# homeboard7.net
KiCad netlist of a schematic drawn in EAGLE
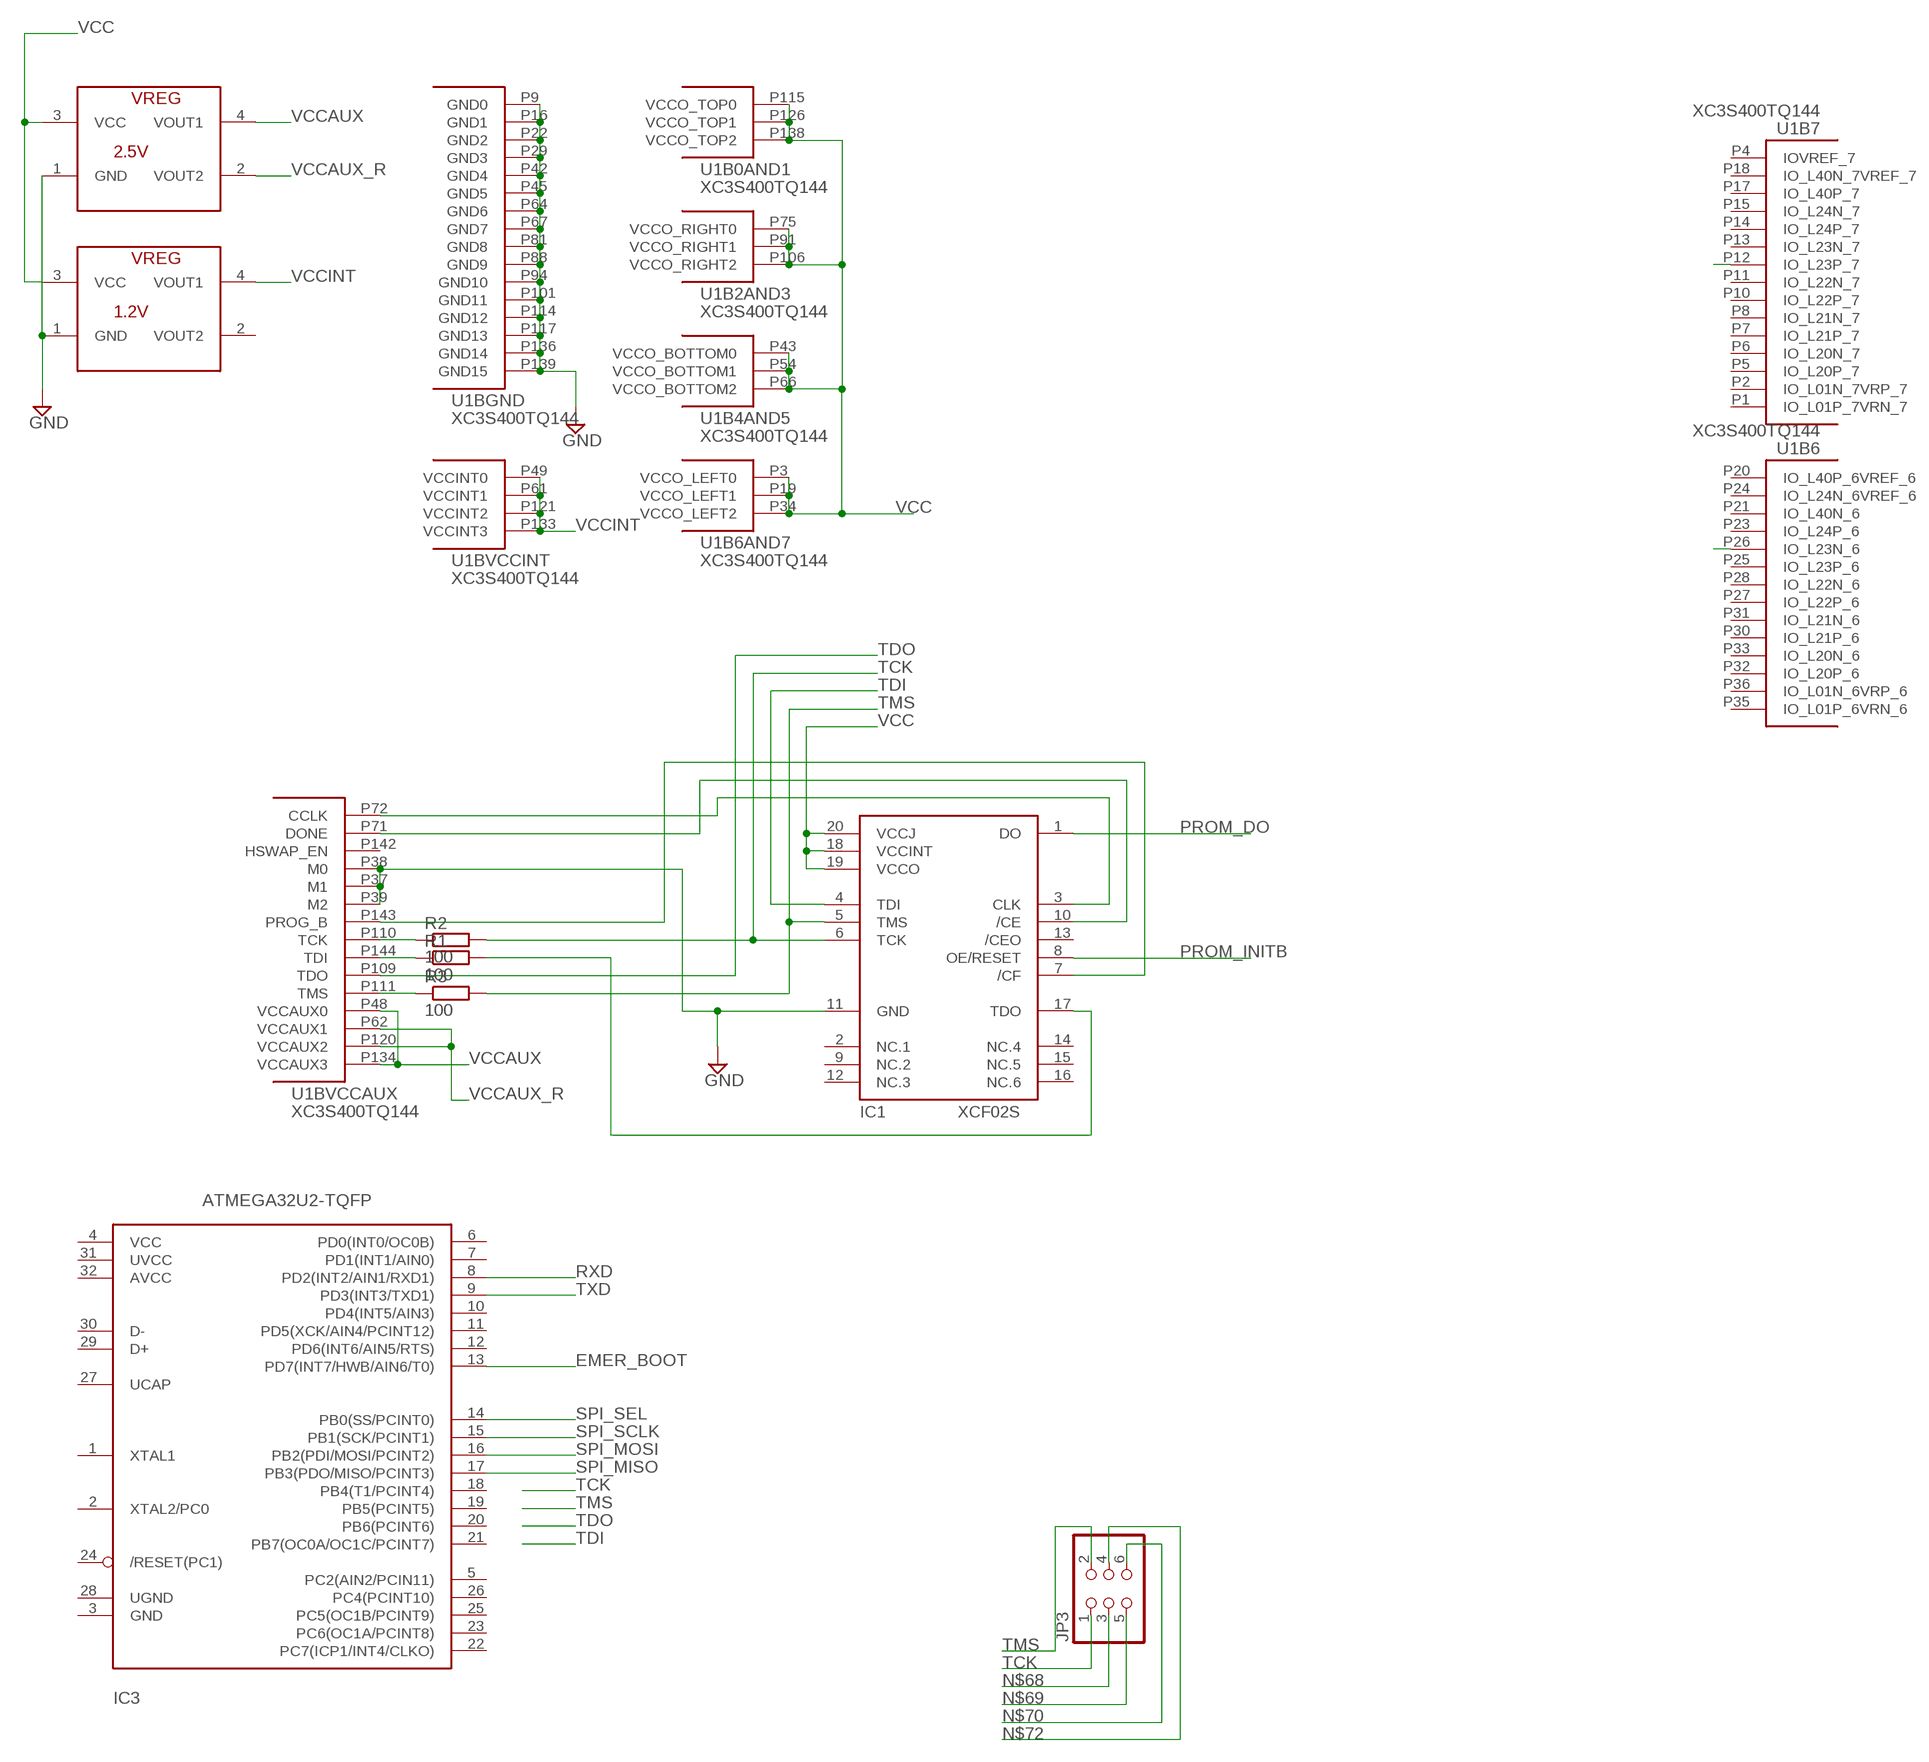
[diagram p0: schematic, sheet 1, part 1 of 3]
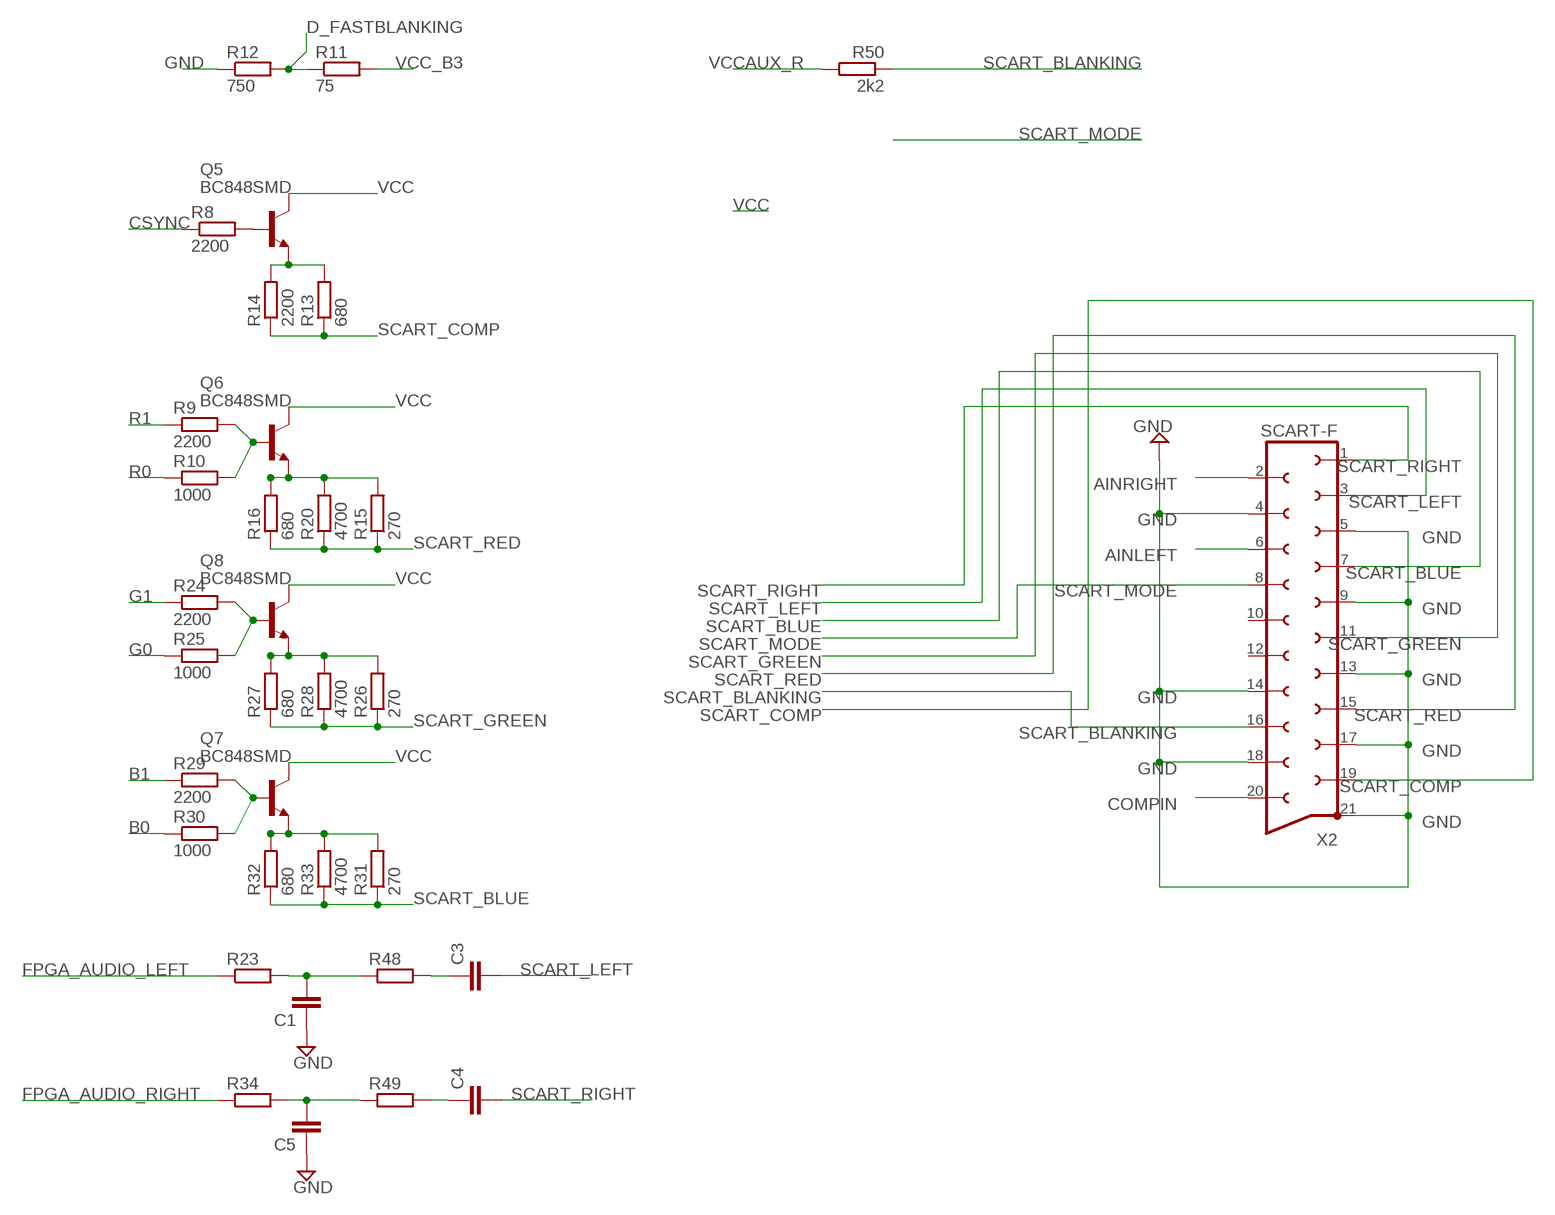
[diagram p1: schematic, sheet 1, part 2 of 3]
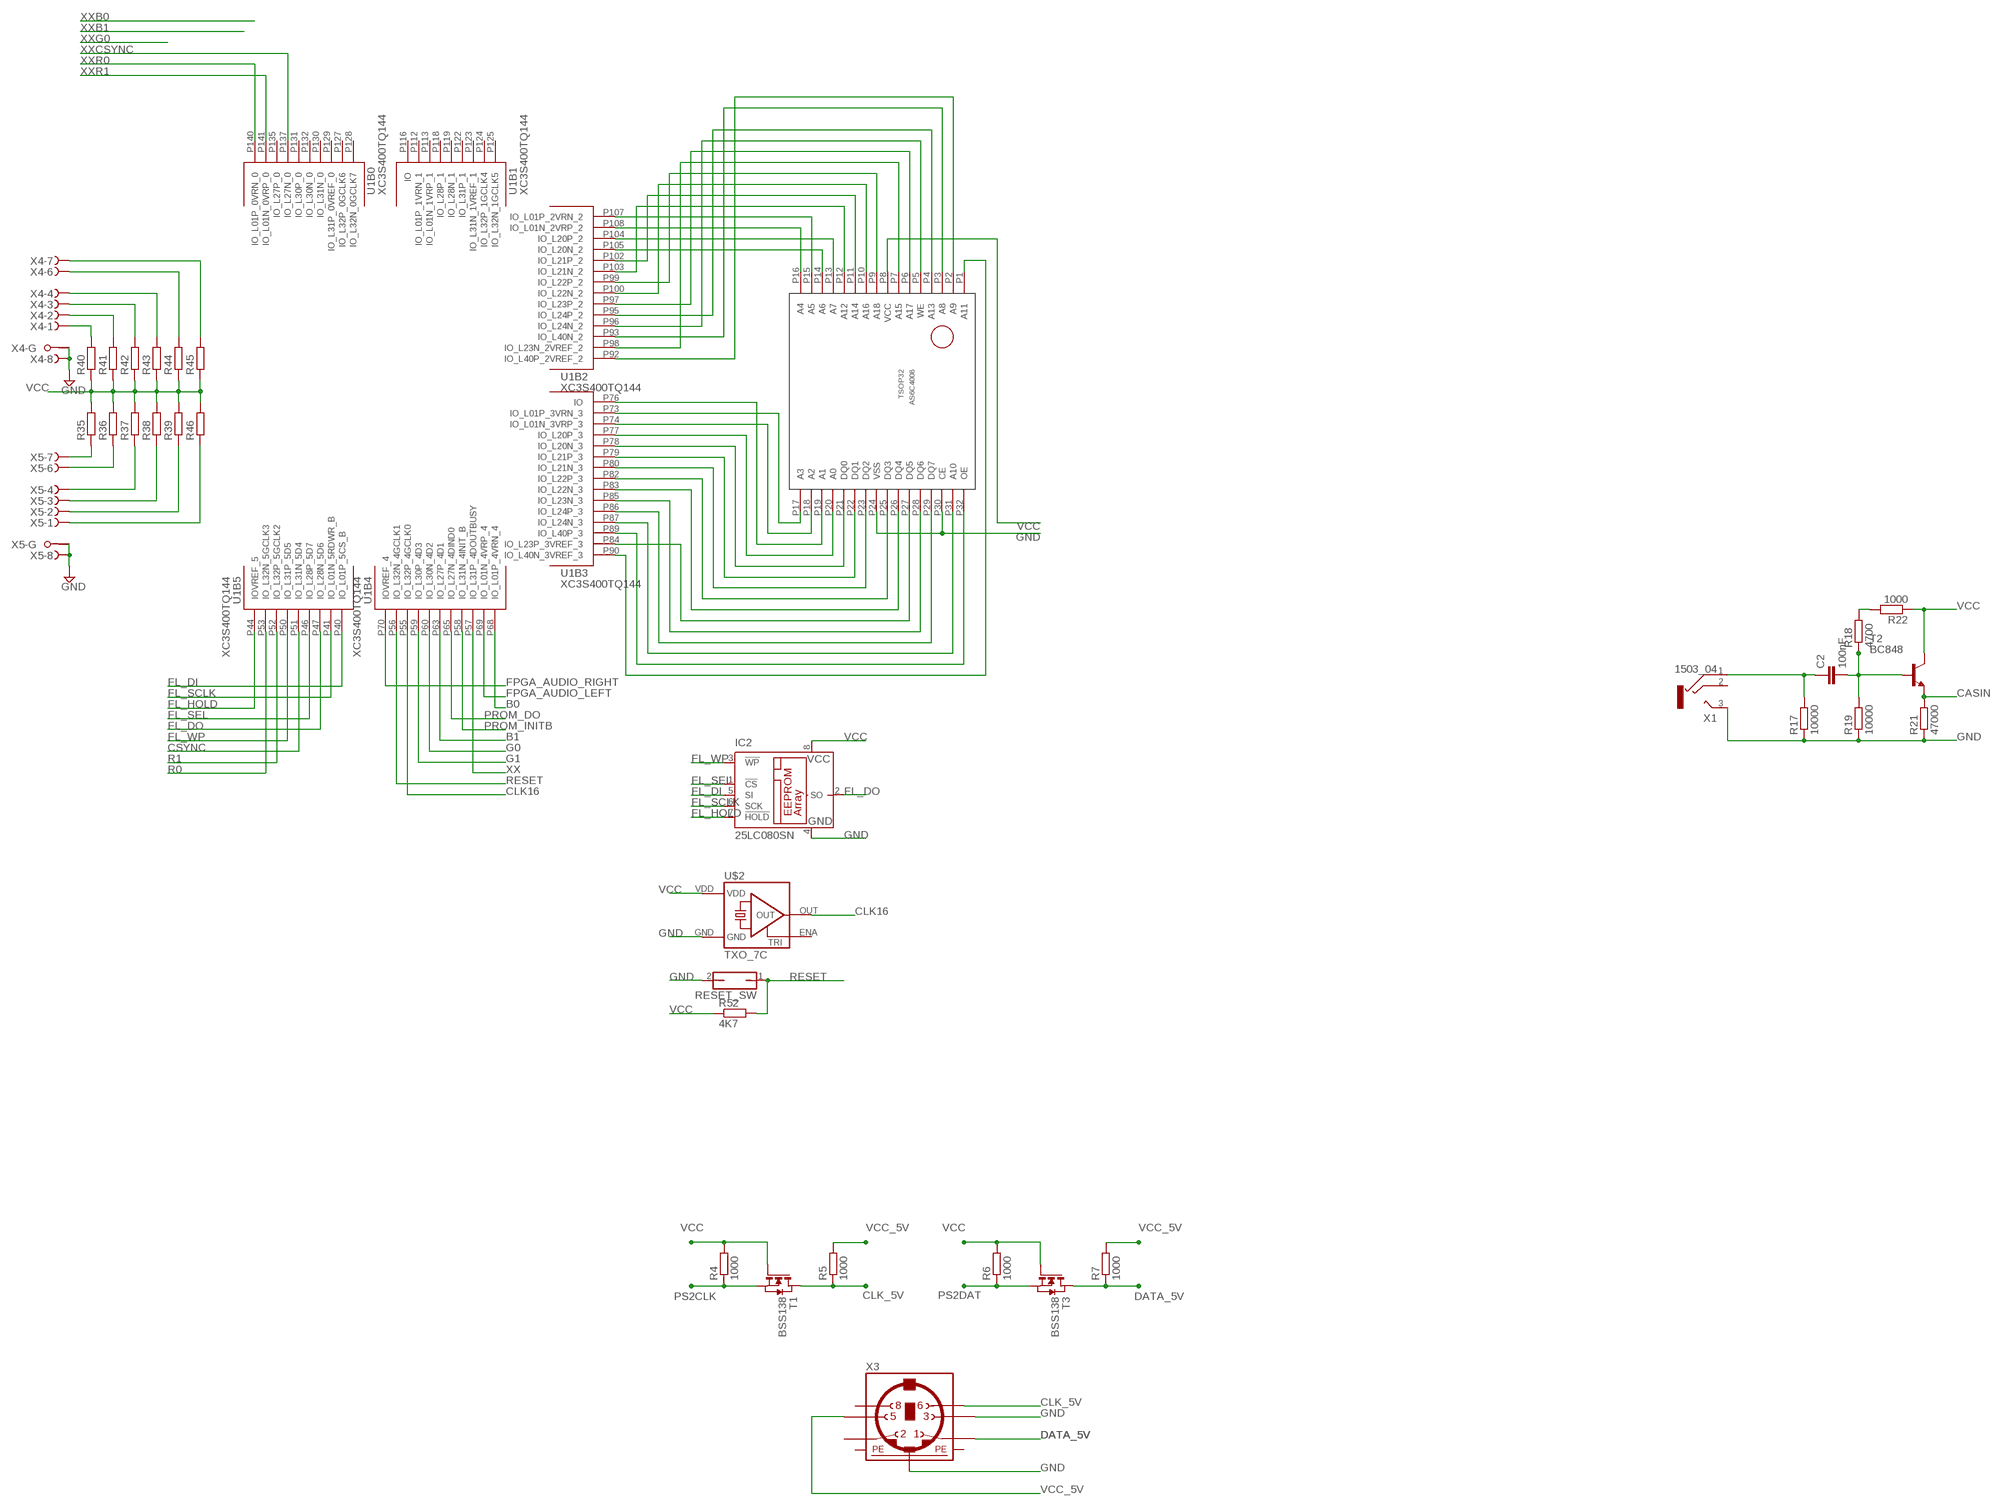
[diagram p2: schematic, sheet 1, part 3 of 3]

(export (version "E")
  (design (tool "Eeschema 10.0.6"))
  (components
    (comp (ref "C1")
      (value "C-EUC0603")
      (footprint "eagle-import:C0603")
      (libsource (lib "eagle-import") (part "C-EUC0603"))
    )
    (comp (ref "C2")
      (value "100nF")
      (footprint "eagle-import:C0603")
      (libsource (lib "eagle-import") (part "C-EUC0603"))
    )
    (comp (ref "C3")
      (value "C-EUC0603")
      (footprint "eagle-import:C0603")
      (libsource (lib "eagle-import") (part "C-EUC0603"))
    )
    (comp (ref "C4")
      (value "C-EUC0603")
      (footprint "eagle-import:C0603")
      (libsource (lib "eagle-import") (part "C-EUC0603"))
    )
    (comp (ref "C5")
      (value "C-EUC0603")
      (footprint "eagle-import:C0603")
      (libsource (lib "eagle-import") (part "C-EUC0603"))
    )
    (comp (ref "IC1")
      (value "XCF02S")
      (footprint "eagle-import:VO20")
      (libsource (lib "eagle-import") (part "XCF02S"))
    )
    (comp (ref "IC2")
      (value "25LC080SN")
      (footprint "eagle-import:SO-08")
      (fields (field (name "MF") "MICROCHIP") (field (name "MPN") "25LC080/SN"))
      (libsource (lib "eagle-import") (part "25SNLC080"))
    )
    (comp (ref "IC3")
      (value "ATMEGA32U2-TQFP")
      (footprint "eagle-import:TQFP32-08")
      (libsource (lib "eagle-import") (part "ATMEGA32U2-TQFP"))
    )
    (comp (ref "JP3")
      (value "PINHD-2X3")
      (footprint "eagle-import:2X03")
      (libsource (lib "eagle-import") (part "PINHD-2X3"))
    )
    (comp (ref "Q5")
      (value "BC848SMD")
      (footprint "eagle-import:SOT23")
      (libsource (lib "eagle-import") (part "BC848SMD"))
    )
    (comp (ref "Q6")
      (value "BC848SMD")
      (footprint "eagle-import:SOT23")
      (libsource (lib "eagle-import") (part "BC848SMD"))
    )
    (comp (ref "Q7")
      (value "BC848SMD")
      (footprint "eagle-import:SOT23")
      (libsource (lib "eagle-import") (part "BC848SMD"))
    )
    (comp (ref "Q8")
      (value "BC848SMD")
      (footprint "eagle-import:SOT23")
      (libsource (lib "eagle-import") (part "BC848SMD"))
    )
    (comp (ref "R1")
      (value "100")
      (footprint "eagle-import:R0805")
      (libsource (lib "eagle-import") (part "R-EU_R0805"))
    )
    (comp (ref "R2")
      (value "100")
      (footprint "eagle-import:R0805")
      (libsource (lib "eagle-import") (part "R-EU_R0805"))
    )
    (comp (ref "R3")
      (value "100")
      (footprint "eagle-import:R0805")
      (libsource (lib "eagle-import") (part "R-EU_R0805"))
    )
    (comp (ref "R4")
      (value "1000")
      (footprint "eagle-import:R0805")
      (libsource (lib "eagle-import") (part "R-EU_R0805"))
    )
    (comp (ref "R5")
      (value "1000")
      (footprint "eagle-import:R0805")
      (libsource (lib "eagle-import") (part "R-EU_R0805"))
    )
    (comp (ref "R6")
      (value "1000")
      (footprint "eagle-import:R0805")
      (libsource (lib "eagle-import") (part "R-EU_R0805"))
    )
    (comp (ref "R7")
      (value "1000")
      (footprint "eagle-import:R0805")
      (libsource (lib "eagle-import") (part "R-EU_R0805"))
    )
    (comp (ref "R8")
      (value "2200")
      (footprint "eagle-import:R0805")
      (libsource (lib "eagle-import") (part "R-EU_R0805"))
    )
    (comp (ref "R9")
      (value "2200")
      (footprint "eagle-import:R0805")
      (libsource (lib "eagle-import") (part "R-EU_R0805"))
    )
    (comp (ref "R10")
      (value "1000")
      (footprint "eagle-import:R0805")
      (libsource (lib "eagle-import") (part "R-EU_R0805"))
    )
    (comp (ref "R11")
      (value "75")
      (footprint "eagle-import:R0805")
      (libsource (lib "eagle-import") (part "R-EU_R0805"))
    )
    (comp (ref "R12")
      (value "750")
      (footprint "eagle-import:R0805")
      (libsource (lib "eagle-import") (part "R-EU_R0805"))
    )
    (comp (ref "R13")
      (value "680")
      (footprint "eagle-import:R0805")
      (libsource (lib "eagle-import") (part "R-EU_R0805"))
    )
    (comp (ref "R14")
      (value "2200")
      (footprint "eagle-import:R0805")
      (libsource (lib "eagle-import") (part "R-EU_R0805"))
    )
    (comp (ref "R15")
      (value "270")
      (footprint "eagle-import:R0805")
      (libsource (lib "eagle-import") (part "R-EU_R0805"))
    )
    (comp (ref "R16")
      (value "680")
      (footprint "eagle-import:R0805")
      (libsource (lib "eagle-import") (part "R-EU_R0805"))
    )
    (comp (ref "R17")
      (value "10000")
      (footprint "eagle-import:R0805")
      (libsource (lib "eagle-import") (part "R-EU_R0805"))
    )
    (comp (ref "R18")
      (value "4700")
      (footprint "eagle-import:R0805")
      (libsource (lib "eagle-import") (part "R-EU_R0805"))
    )
    (comp (ref "R19")
      (value "10000")
      (footprint "eagle-import:R0805")
      (libsource (lib "eagle-import") (part "R-EU_R0805"))
    )
    (comp (ref "R20")
      (value "4700")
      (footprint "eagle-import:R0805")
      (libsource (lib "eagle-import") (part "R-EU_R0805"))
    )
    (comp (ref "R21")
      (value "47000")
      (footprint "eagle-import:R0805")
      (libsource (lib "eagle-import") (part "R-EU_R0805"))
    )
    (comp (ref "R22")
      (value "1000")
      (footprint "eagle-import:R0805")
      (libsource (lib "eagle-import") (part "R-EU_R0805"))
    )
    (comp (ref "R23")
      (value "R-EU_M0805")
      (footprint "eagle-import:M0805")
      (libsource (lib "eagle-import") (part "resistor_R-EU_M0805"))
    )
    (comp (ref "R24")
      (value "2200")
      (footprint "eagle-import:R0805")
      (libsource (lib "eagle-import") (part "R-EU_R0805"))
    )
    (comp (ref "R25")
      (value "1000")
      (footprint "eagle-import:R0805")
      (libsource (lib "eagle-import") (part "R-EU_R0805"))
    )
    (comp (ref "R26")
      (value "270")
      (footprint "eagle-import:R0805")
      (libsource (lib "eagle-import") (part "R-EU_R0805"))
    )
    (comp (ref "R27")
      (value "680")
      (footprint "eagle-import:R0805")
      (libsource (lib "eagle-import") (part "R-EU_R0805"))
    )
    (comp (ref "R28")
      (value "4700")
      (footprint "eagle-import:R0805")
      (libsource (lib "eagle-import") (part "R-EU_R0805"))
    )
    (comp (ref "R29")
      (value "2200")
      (footprint "eagle-import:R0805")
      (libsource (lib "eagle-import") (part "R-EU_R0805"))
    )
    (comp (ref "R30")
      (value "1000")
      (footprint "eagle-import:R0805")
      (libsource (lib "eagle-import") (part "R-EU_R0805"))
    )
    (comp (ref "R31")
      (value "270")
      (footprint "eagle-import:R0805")
      (libsource (lib "eagle-import") (part "R-EU_R0805"))
    )
    (comp (ref "R32")
      (value "680")
      (footprint "eagle-import:R0805")
      (libsource (lib "eagle-import") (part "R-EU_R0805"))
    )
    (comp (ref "R33")
      (value "4700")
      (footprint "eagle-import:R0805")
      (libsource (lib "eagle-import") (part "R-EU_R0805"))
    )
    (comp (ref "R34")
      (value "R-EU_M0805")
      (footprint "eagle-import:M0805")
      (libsource (lib "eagle-import") (part "resistor_R-EU_M0805"))
    )
    (comp (ref "R35")
      (value "R-EU_M0805")
      (footprint "eagle-import:M0805")
      (libsource (lib "eagle-import") (part "resistor_R-EU_M0805"))
    )
    (comp (ref "R36")
      (value "R-EU_M0805")
      (footprint "eagle-import:M0805")
      (libsource (lib "eagle-import") (part "resistor_R-EU_M0805"))
    )
    (comp (ref "R37")
      (value "R-EU_M0805")
      (footprint "eagle-import:M0805")
      (libsource (lib "eagle-import") (part "resistor_R-EU_M0805"))
    )
    (comp (ref "R38")
      (value "R-EU_M0805")
      (footprint "eagle-import:M0805")
      (libsource (lib "eagle-import") (part "resistor_R-EU_M0805"))
    )
    (comp (ref "R39")
      (value "R-EU_M0805")
      (footprint "eagle-import:M0805")
      (libsource (lib "eagle-import") (part "resistor_R-EU_M0805"))
    )
    (comp (ref "R40")
      (value "R-EU_M0805")
      (footprint "eagle-import:M0805")
      (libsource (lib "eagle-import") (part "resistor_R-EU_M0805"))
    )
    (comp (ref "R41")
      (value "R-EU_M0805")
      (footprint "eagle-import:M0805")
      (libsource (lib "eagle-import") (part "resistor_R-EU_M0805"))
    )
    (comp (ref "R42")
      (value "R-EU_M0805")
      (footprint "eagle-import:M0805")
      (libsource (lib "eagle-import") (part "resistor_R-EU_M0805"))
    )
    (comp (ref "R43")
      (value "R-EU_M0805")
      (footprint "eagle-import:M0805")
      (libsource (lib "eagle-import") (part "resistor_R-EU_M0805"))
    )
    (comp (ref "R44")
      (value "R-EU_M0805")
      (footprint "eagle-import:M0805")
      (libsource (lib "eagle-import") (part "resistor_R-EU_M0805"))
    )
    (comp (ref "R45")
      (value "R-EU_M0805")
      (footprint "eagle-import:M0805")
      (libsource (lib "eagle-import") (part "resistor_R-EU_M0805"))
    )
    (comp (ref "R46")
      (value "R-EU_M0805")
      (footprint "eagle-import:M0805")
      (libsource (lib "eagle-import") (part "resistor_R-EU_M0805"))
    )
    (comp (ref "R48")
      (value "R-EU_M0805")
      (footprint "eagle-import:M0805")
      (libsource (lib "eagle-import") (part "resistor_R-EU_M0805"))
    )
    (comp (ref "R49")
      (value "R-EU_M0805")
      (footprint "eagle-import:M0805")
      (libsource (lib "eagle-import") (part "resistor_R-EU_M0805"))
    )
    (comp (ref "R50")
      (value "2k2")
      (footprint "eagle-import:M0805")
      (libsource (lib "eagle-import") (part "resistor_R-EU_M0805"))
    )
    (comp (ref "R52")
      (value "4K7")
      (footprint "eagle-import:M0805")
      (libsource (lib "eagle-import") (part "resistor_R-EU_M0805"))
    )
    (comp (ref "REG1.2")
      (value "1.2V")
      (footprint "eagle-import:SOT223")
      (libsource (lib "eagle-import") (part "NX1117"))
    )
    (comp (ref "REG2.5")
      (value "2.5V")
      (footprint "eagle-import:SOT223")
      (libsource (lib "eagle-import") (part "NX1117"))
    )
    (comp (ref "RESET_SW")
      (value "JP1Q")
      (footprint "eagle-import:JP1")
      (libsource (lib "eagle-import") (part "JP1Q"))
    )
    (comp (ref "T1")
      (value "BSS138")
      (footprint "eagle-import:SOT-23")
      (libsource (lib "eagle-import") (part "NMOSSOT23"))
    )
    (comp (ref "T2")
      (value "BC848")
      (footprint "eagle-import:SOT23")
      (libsource (lib "eagle-import") (part "BC848"))
    )
    (comp (ref "T3")
      (value "BSS138")
      (footprint "eagle-import:SOT-23")
      (libsource (lib "eagle-import") (part "NMOSSOT23"))
    )
    (comp (ref "U$1")
      (value "AS6C4008")
      (footprint "eagle-import:TSOP32")
      (libsource (lib "eagle-import") (part "AS6C4008"))
    )
    (comp (ref "U$2")
      (value "TXO_7C")
      (footprint "eagle-import:OSC_7C")
      (libsource (lib "eagle-import") (part "TXO_7C"))
    )
    (comp (ref "U1")
      (value "XC3S400TQ144")
      (footprint "eagle-import:TQ144")
      (libsource (lib "eagle-import") (part "XC3S400TQ144"))
    )
    (comp (ref "X1")
      (value "1503_04")
      (footprint "eagle-import:1503_04")
      (libsource (lib "eagle-import") (part "1503_04"))
    )
    (comp (ref "X2")
      (value "SCART-F")
      (footprint "eagle-import:SCART-F")
      (libsource (lib "eagle-import") (part "SCART-F"))
    )
    (comp (ref "X3")
      (value "MINI_DIN_6")
      (footprint "eagle-import:M_DIN6")
      (libsource (lib "eagle-import") (part "MINI_DIN_6"))
    )
    (comp (ref "X4")
      (value "F09HPS")
      (footprint "eagle-import:F09HP")
      (libsource (lib "eagle-import") (part "F09HPS"))
    )
    (comp (ref "X5")
      (value "F09HPS")
      (footprint "eagle-import:F09HP")
      (libsource (lib "eagle-import") (part "F09HPS"))
    )
  )
  (nets
    (net (code "1") (name "/AINLEFT") (class "Default")
      (node (ref "X2") (pin "6") (pinfunction "6_6") (pintype "passive"))
    )
    (net (code "2") (name "/AINRIGHT") (class "Default")
      (node (ref "X2") (pin "2") (pinfunction "2_2") (pintype "passive"))
    )
    (net (code "3") (name "/B0") (class "Default")
      (node (ref "R30") (pin "1") (pinfunction "1_1") (pintype "passive"))
      (node (ref "U1") (pin "P68") (pinfunction "IO_L01P_4VRN_4_P68") (pintype "bidirectional"))
    )
    (net (code "4") (name "/B1") (class "Default")
      (node (ref "R29") (pin "1") (pinfunction "1_1") (pintype "passive"))
      (node (ref "U1") (pin "P63") (pinfunction "IO_L27P_4D1_P63") (pintype "bidirectional"))
    )
    (net (code "5") (name "/CASIN") (class "Default")
      (node (ref "R21") (pin "2") (pinfunction "2_2") (pintype "passive"))
      (node (ref "T2") (pin "2") (pinfunction "E_2") (pintype "passive"))
    )
    (net (code "6") (name "/CLK16") (class "Default")
      (node (ref "U$2") (pin "OUT") (pinfunction "OUT_OUT") (pintype "output"))
      (node (ref "U1") (pin "P55") (pinfunction "IO_L32P_4GCLK0_P55") (pintype "bidirectional"))
    )
    (net (code "7") (name "/CLK_5V") (class "Default")
      (node (ref "R5") (pin "1") (pinfunction "1_1") (pintype "passive"))
      (node (ref "T1") (pin "1") (pinfunction "D_1") (pintype "passive"))
      (node (ref "X3") (pin "6") (pinfunction "6_6") (pintype "passive"))
    )
    (net (code "8") (name "/COMPIN") (class "Default")
      (node (ref "X2") (pin "20") (pinfunction "20_20") (pintype "passive"))
    )
    (net (code "9") (name "/CSYNC") (class "Default")
      (node (ref "R8") (pin "1") (pinfunction "1_1") (pintype "passive"))
      (node (ref "U1") (pin "P51") (pinfunction "IO_L31N_5D4_P51") (pintype "bidirectional"))
    )
    (net (code "10") (name "/DATA_5V") (class "Default")
      (node (ref "R7") (pin "1") (pinfunction "1_1") (pintype "passive"))
      (node (ref "T3") (pin "1") (pinfunction "D_1") (pintype "passive"))
      (node (ref "X3") (pin "1") (pinfunction "1_1") (pintype "passive"))
    )
    (net (code "11") (name "/D_FASTBLANKING") (class "Default")
      (node (ref "R11") (pin "1") (pinfunction "1_1") (pintype "passive"))
      (node (ref "R12") (pin "2") (pinfunction "2_2") (pintype "passive"))
    )
    (net (code "12") (name "/EMER_BOOT") (class "Default")
      (node (ref "IC3") (pin "13") (pinfunction "PD7(INT7/HWB/AIN6/T0)_13") (pintype "bidirectional"))
    )
    (net (code "13") (name "/FL_DI") (class "Default")
      (node (ref "IC2") (pin "5") (pinfunction "SI_5") (pintype "input"))
      (node (ref "U1") (pin "P40") (pinfunction "IO_L01P_5CS_B_P40") (pintype "bidirectional"))
    )
    (net (code "14") (name "/FL_DO") (class "Default")
      (node (ref "IC2") (pin "2") (pinfunction "SO_2") (pintype "bidirectional"))
      (node (ref "U1") (pin "P47") (pinfunction "IO_L28N_5D6_P47") (pintype "bidirectional"))
    )
    (net (code "15") (name "/FL_HOLD") (class "Default")
      (node (ref "IC2") (pin "7") (pinfunction "~{HOLD}_7") (pintype "input"))
      (node (ref "U1") (pin "P44") (pinfunction "IOVREF_5_P44") (pintype "bidirectional"))
    )
    (net (code "16") (name "/FL_SCLK") (class "Default")
      (node (ref "IC2") (pin "6") (pinfunction "SCK_6") (pintype "input"))
      (node (ref "U1") (pin "P41") (pinfunction "IO_L01N_5RDWR_B_P41") (pintype "bidirectional"))
    )
    (net (code "17") (name "/FL_SEL") (class "Default")
      (node (ref "IC2") (pin "1") (pinfunction "~{CS}_1") (pintype "input"))
      (node (ref "U1") (pin "P46") (pinfunction "IO_L28P_5D7_P46") (pintype "bidirectional"))
    )
    (net (code "18") (name "/FL_WP") (class "Default")
      (node (ref "IC2") (pin "3") (pinfunction "~{WP}_3") (pintype "input"))
      (node (ref "U1") (pin "P50") (pinfunction "IO_L31P_5D5_P50") (pintype "bidirectional"))
    )
    (net (code "19") (name "/FPGA_AUDIO_LEFT") (class "Default")
      (node (ref "R23") (pin "1") (pinfunction "1_1") (pintype "passive"))
      (node (ref "U1") (pin "P69") (pinfunction "IO_L01N_4VRP_4_P69") (pintype "bidirectional"))
    )
    (net (code "20") (name "/FPGA_AUDIO_RIGHT") (class "Default")
      (node (ref "R34") (pin "1") (pinfunction "1_1") (pintype "passive"))
      (node (ref "U1") (pin "P70") (pinfunction "IOVREF_4_P70") (pintype "bidirectional"))
    )
    (net (code "21") (name "/G0") (class "Default")
      (node (ref "R25") (pin "1") (pinfunction "1_1") (pintype "passive"))
      (node (ref "U1") (pin "P60") (pinfunction "IO_L30N_4D2_P60") (pintype "bidirectional"))
    )
    (net (code "22") (name "/G1") (class "Default")
      (node (ref "R24") (pin "1") (pinfunction "1_1") (pintype "passive"))
      (node (ref "U1") (pin "P59") (pinfunction "IO_L30P_4D3_P59") (pintype "bidirectional"))
    )
    (net (code "23") (name "/N$68") (class "Default")
      (node (ref "JP3") (pin "3") (pinfunction "3_3") (pintype "passive"))
    )
    (net (code "24") (name "/N$69") (class "Default")
      (node (ref "JP3") (pin "5") (pinfunction "5_5") (pintype "passive"))
    )
    (net (code "25") (name "/N$70") (class "Default")
      (node (ref "JP3") (pin "6") (pinfunction "6_6") (pintype "passive"))
    )
    (net (code "26") (name "/N$72") (class "Default")
      (node (ref "JP3") (pin "4") (pinfunction "4_4") (pintype "passive"))
    )
    (net (code "27") (name "/PE1") (class "Default")
      (node (ref "X3") (pin "SH1") (pinfunction "PE1_SH1") (pintype "power_in"))
    )
    (net (code "28") (name "/PE3") (class "Default")
      (node (ref "X3") (pin "SH3") (pinfunction "PE3_SH3") (pintype "power_in"))
    )
    (net (code "29") (name "/PROM_DO") (class "Default")
      (node (ref "IC1") (pin "1") (pinfunction "DO_1") (pintype "bidirectional"))
      (node (ref "U1") (pin "P65") (pinfunction "IO_L27N_4DIND0_P65") (pintype "bidirectional"))
    )
    (net (code "30") (name "/PROM_INITB") (class "Default")
      (node (ref "IC1") (pin "8") (pinfunction "OE/RESET_8") (pintype "bidirectional"))
      (node (ref "U1") (pin "P58") (pinfunction "IO_L31N_4INIT_B_P58") (pintype "bidirectional"))
    )
    (net (code "31") (name "/PS2CLK") (class "Default")
      (node (ref "R4") (pin "1") (pinfunction "1_1") (pintype "passive"))
      (node (ref "T1") (pin "2") (pinfunction "S_2") (pintype "passive"))
    )
    (net (code "32") (name "/PS2DAT") (class "Default")
      (node (ref "R6") (pin "1") (pinfunction "1_1") (pintype "passive"))
      (node (ref "T3") (pin "2") (pinfunction "S_2") (pintype "passive"))
    )
    (net (code "33") (name "/R0") (class "Default")
      (node (ref "R10") (pin "1") (pinfunction "1_1") (pintype "passive"))
      (node (ref "U1") (pin "P53") (pinfunction "IO_L32N_5GCLK3_P53") (pintype "bidirectional"))
    )
    (net (code "34") (name "/R1") (class "Default")
      (node (ref "R9") (pin "1") (pinfunction "1_1") (pintype "passive"))
      (node (ref "U1") (pin "P52") (pinfunction "IO_L32P_5GCLK2_P52") (pintype "bidirectional"))
    )
    (net (code "35") (name "/RESET") (class "Default")
      (node (ref "R52") (pin "2") (pinfunction "2_2") (pintype "passive"))
      (node (ref "RESET_SW") (pin "1") (pinfunction "1_1") (pintype "passive"))
      (node (ref "U1") (pin "P56") (pinfunction "IO_L32N_4GCLK1_P56") (pintype "bidirectional"))
    )
    (net (code "36") (name "/RXD") (class "Default")
      (node (ref "IC3") (pin "8") (pinfunction "PD2(INT2/AIN1/RXD1)_8") (pintype "bidirectional"))
    )
    (net (code "37") (name "/SCART_BLANKING") (class "Default")
      (node (ref "R50") (pin "1") (pinfunction "1_1") (pintype "passive"))
      (node (ref "X2") (pin "16") (pinfunction "16_16") (pintype "passive"))
    )
    (net (code "38") (name "/SCART_BLUE") (class "Default")
      (node (ref "R31") (pin "1") (pinfunction "1_1") (pintype "passive"))
      (node (ref "R32") (pin "1") (pinfunction "1_1") (pintype "passive"))
      (node (ref "R33") (pin "1") (pinfunction "1_1") (pintype "passive"))
      (node (ref "X2") (pin "7") (pinfunction "7_7") (pintype "passive"))
    )
    (net (code "39") (name "/SCART_COMP") (class "Default")
      (node (ref "R13") (pin "1") (pinfunction "1_1") (pintype "passive"))
      (node (ref "R14") (pin "1") (pinfunction "1_1") (pintype "passive"))
      (node (ref "X2") (pin "19") (pinfunction "19_19") (pintype "passive"))
    )
    (net (code "40") (name "/SCART_GREEN") (class "Default")
      (node (ref "R26") (pin "1") (pinfunction "1_1") (pintype "passive"))
      (node (ref "R27") (pin "1") (pinfunction "1_1") (pintype "passive"))
      (node (ref "R28") (pin "1") (pinfunction "1_1") (pintype "passive"))
      (node (ref "X2") (pin "11") (pinfunction "11_11") (pintype "passive"))
    )
    (net (code "41") (name "/SCART_LEFT") (class "Default")
      (node (ref "C3") (pin "2") (pinfunction "2_2") (pintype "passive"))
      (node (ref "X2") (pin "3") (pinfunction "3_3") (pintype "passive"))
    )
    (net (code "42") (name "/SCART_MODE") (class "Default")
      (node (ref "X2") (pin "8") (pinfunction "8_8") (pintype "passive"))
    )
    (net (code "43") (name "/SCART_RED") (class "Default")
      (node (ref "R15") (pin "1") (pinfunction "1_1") (pintype "passive"))
      (node (ref "R16") (pin "1") (pinfunction "1_1") (pintype "passive"))
      (node (ref "R20") (pin "1") (pinfunction "1_1") (pintype "passive"))
      (node (ref "X2") (pin "15") (pinfunction "15_15") (pintype "passive"))
    )
    (net (code "44") (name "/SCART_RIGHT") (class "Default")
      (node (ref "C4") (pin "2") (pinfunction "2_2") (pintype "passive"))
      (node (ref "X2") (pin "1") (pinfunction "1_1") (pintype "passive"))
    )
    (net (code "45") (name "/SPI_MISO") (class "Default")
      (node (ref "IC3") (pin "17") (pinfunction "PB3(PDO/MISO/PCINT3)_17") (pintype "bidirectional"))
    )
    (net (code "46") (name "/SPI_MOSI") (class "Default")
      (node (ref "IC3") (pin "16") (pinfunction "PB2(PDI/MOSI/PCINT2)_16") (pintype "bidirectional"))
    )
    (net (code "47") (name "/SPI_SCLK") (class "Default")
      (node (ref "IC3") (pin "15") (pinfunction "PB1(SCK/PCINT1)_15") (pintype "bidirectional"))
    )
    (net (code "48") (name "/SPI_SEL") (class "Default")
      (node (ref "IC3") (pin "14") (pinfunction "PB0(SS/PCINT0)_14") (pintype "bidirectional"))
    )
    (net (code "49") (name "/TCK") (class "Default")
      (node (ref "IC1") (pin "6") (pinfunction "TCK_6") (pintype "bidirectional"))
      (node (ref "JP3") (pin "1") (pinfunction "1_1") (pintype "passive"))
      (node (ref "R2") (pin "2") (pinfunction "2_2") (pintype "passive"))
    )
    (net (code "50") (name "/TDI") (class "Default")
      (node (ref "IC1") (pin "4") (pinfunction "TDI_4") (pintype "bidirectional"))
    )
    (net (code "51") (name "/TDO") (class "Default")
      (node (ref "U1") (pin "P109") (pinfunction "TDO_P109") (pintype "bidirectional"))
    )
    (net (code "52") (name "/TMS") (class "Default")
      (node (ref "IC1") (pin "5") (pinfunction "TMS_5") (pintype "bidirectional"))
      (node (ref "JP3") (pin "2") (pinfunction "2_2") (pintype "passive"))
      (node (ref "R3") (pin "2") (pinfunction "2_2") (pintype "passive"))
    )
    (net (code "53") (name "/TXD") (class "Default")
      (node (ref "IC3") (pin "9") (pinfunction "PD3(INT3/TXD1)_9") (pintype "bidirectional"))
    )
    (net (code "54") (name "/VCC") (class "Default")
      (node (ref "IC1") (pin "18") (pinfunction "VCCINT_18") (pintype "bidirectional"))
      (node (ref "IC1") (pin "19") (pinfunction "VCCO_19") (pintype "bidirectional"))
      (node (ref "IC1") (pin "20") (pinfunction "VCCJ_20") (pintype "bidirectional"))
      (node (ref "IC2") (pin "8") (pinfunction "VCC_8") (pintype "power_in"))
      (node (ref "Q5") (pin "3") (pinfunction "C_3") (pintype "passive"))
      (node (ref "Q6") (pin "3") (pinfunction "C_3") (pintype "passive"))
      (node (ref "Q7") (pin "3") (pinfunction "C_3") (pintype "passive"))
      (node (ref "Q8") (pin "3") (pinfunction "C_3") (pintype "passive"))
      (node (ref "R22") (pin "1") (pinfunction "1_1") (pintype "passive"))
      (node (ref "R35") (pin "2") (pinfunction "2_2") (pintype "passive"))
      (node (ref "R36") (pin "2") (pinfunction "2_2") (pintype "passive"))
      (node (ref "R37") (pin "2") (pinfunction "2_2") (pintype "passive"))
      (node (ref "R38") (pin "2") (pinfunction "2_2") (pintype "passive"))
      (node (ref "R39") (pin "2") (pinfunction "2_2") (pintype "passive"))
      (node (ref "R4") (pin "2") (pinfunction "2_2") (pintype "passive"))
      (node (ref "R40") (pin "1") (pinfunction "1_1") (pintype "passive"))
      (node (ref "R41") (pin "1") (pinfunction "1_1") (pintype "passive"))
      (node (ref "R42") (pin "1") (pinfunction "1_1") (pintype "passive"))
      (node (ref "R43") (pin "1") (pinfunction "1_1") (pintype "passive"))
      (node (ref "R44") (pin "1") (pinfunction "1_1") (pintype "passive"))
      (node (ref "R45") (pin "1") (pinfunction "1_1") (pintype "passive"))
      (node (ref "R46") (pin "2") (pinfunction "2_2") (pintype "passive"))
      (node (ref "R52") (pin "1") (pinfunction "1_1") (pintype "passive"))
      (node (ref "R6") (pin "2") (pinfunction "2_2") (pintype "passive"))
      (node (ref "REG1.2") (pin "3") (pinfunction "VCC_3") (pintype "bidirectional"))
      (node (ref "REG2.5") (pin "3") (pinfunction "VCC_3") (pintype "bidirectional"))
      (node (ref "T1") (pin "3") (pinfunction "G_3") (pintype "passive"))
      (node (ref "T2") (pin "3") (pinfunction "C_3") (pintype "passive"))
      (node (ref "T3") (pin "3") (pinfunction "G_3") (pintype "passive"))
      (node (ref "U$1") (pin "P8") (pinfunction "VCC_P8") (pintype "bidirectional"))
      (node (ref "U$2") (pin "VDD") (pinfunction "VDD_VDD") (pintype "power_in"))
      (node (ref "U1") (pin "P106") (pinfunction "VCCO_RIGHT2_P106") (pintype "passive"))
      (node (ref "U1") (pin "P115") (pinfunction "VCCO_TOP0_P115") (pintype "passive"))
      (node (ref "U1") (pin "P126") (pinfunction "VCCO_TOP1_P126") (pintype "passive"))
      (node (ref "U1") (pin "P138") (pinfunction "VCCO_TOP2_P138") (pintype "passive"))
      (node (ref "U1") (pin "P19") (pinfunction "VCCO_LEFT1_P19") (pintype "passive"))
      (node (ref "U1") (pin "P3") (pinfunction "VCCO_LEFT0_P3") (pintype "passive"))
      (node (ref "U1") (pin "P34") (pinfunction "VCCO_LEFT2_P34") (pintype "passive"))
      (node (ref "U1") (pin "P43") (pinfunction "VCCO_BOTTOM0_P43") (pintype "passive"))
      (node (ref "U1") (pin "P54") (pinfunction "VCCO_BOTTOM1_P54") (pintype "passive"))
      (node (ref "U1") (pin "P66") (pinfunction "VCCO_BOTTOM2_P66") (pintype "passive"))
      (node (ref "U1") (pin "P75") (pinfunction "VCCO_RIGHT0_P75") (pintype "passive"))
      (node (ref "U1") (pin "P91") (pinfunction "VCCO_RIGHT1_P91") (pintype "passive"))
    )
    (net (code "55") (name "/VCCAUX") (class "Default")
      (node (ref "REG2.5") (pin "4") (pinfunction "VOUT1_4") (pintype "bidirectional"))
      (node (ref "U1") (pin "P134") (pinfunction "VCCAUX3_P134") (pintype "passive"))
      (node (ref "U1") (pin "P48") (pinfunction "VCCAUX0_P48") (pintype "passive"))
    )
    (net (code "56") (name "/VCCAUX_R") (class "Default")
      (node (ref "R50") (pin "2") (pinfunction "2_2") (pintype "passive"))
      (node (ref "REG2.5") (pin "2") (pinfunction "VOUT2_2") (pintype "bidirectional"))
      (node (ref "U1") (pin "P120") (pinfunction "VCCAUX2_P120") (pintype "passive"))
      (node (ref "U1") (pin "P62") (pinfunction "VCCAUX1_P62") (pintype "passive"))
    )
    (net (code "57") (name "/VCCINT") (class "Default")
      (node (ref "REG1.2") (pin "4") (pinfunction "VOUT1_4") (pintype "bidirectional"))
      (node (ref "U1") (pin "P121") (pinfunction "VCCINT2_P121") (pintype "passive"))
      (node (ref "U1") (pin "P133") (pinfunction "VCCINT3_P133") (pintype "passive"))
      (node (ref "U1") (pin "P49") (pinfunction "VCCINT0_P49") (pintype "passive"))
      (node (ref "U1") (pin "P61") (pinfunction "VCCINT1_P61") (pintype "passive"))
    )
    (net (code "58") (name "/VCC_5V") (class "Default")
      (node (ref "R5") (pin "2") (pinfunction "2_2") (pintype "passive"))
      (node (ref "R7") (pin "2") (pinfunction "2_2") (pintype "passive"))
      (node (ref "X3") (pin "5") (pinfunction "5_5") (pintype "passive"))
    )
    (net (code "59") (name "/VCC_B3") (class "Default")
      (node (ref "R11") (pin "2") (pinfunction "2_2") (pintype "passive"))
    )
    (net (code "60") (name "/XX") (class "Default")
      (node (ref "U1") (pin "P57") (pinfunction "IO_L31P_4DOUTBUSY_P57") (pintype "bidirectional"))
    )
    (net (code "63") (name "/XXCSYNC") (class "Default")
      (node (ref "U1") (pin "P137") (pinfunction "IO_L27N_0_P137") (pintype "bidirectional"))
    )
    (net (code "65") (name "/XXR0") (class "Default")
      (node (ref "U1") (pin "P140") (pinfunction "IO_L01P_0VRN_0_P140") (pintype "bidirectional"))
    )
    (net (code "66") (name "/XXR1") (class "Default")
      (node (ref "U1") (pin "P141") (pinfunction "IO_L01N_0VRP_0_P141") (pintype "bidirectional"))
    )
    (net (code "67") (name "GND") (class "Default")
      (node (ref "C1") (pin "1") (pinfunction "1_1") (pintype "passive"))
      (node (ref "C5") (pin "1") (pinfunction "1_1") (pintype "passive"))
      (node (ref "IC1") (pin "11") (pinfunction "GND_11") (pintype "bidirectional"))
      (node (ref "IC2") (pin "4") (pinfunction "GND_4") (pintype "power_in"))
      (node (ref "R12") (pin "1") (pinfunction "1_1") (pintype "passive"))
      (node (ref "R17") (pin "1") (pinfunction "1_1") (pintype "passive"))
      (node (ref "R19") (pin "1") (pinfunction "1_1") (pintype "passive"))
      (node (ref "R21") (pin "1") (pinfunction "1_1") (pintype "passive"))
      (node (ref "REG1.2") (pin "1") (pinfunction "GND_1") (pintype "bidirectional"))
      (node (ref "REG2.5") (pin "1") (pinfunction "GND_1") (pintype "bidirectional"))
      (node (ref "RESET_SW") (pin "2") (pinfunction "2_2") (pintype "passive"))
      (node (ref "U$1") (pin "P24") (pinfunction "VSS_P24") (pintype "bidirectional"))
      (node (ref "U$1") (pin "P30") (pinfunction "CE_P30") (pintype "bidirectional"))
      (node (ref "U$2") (pin "GND") (pinfunction "GND_GND") (pintype "power_in"))
      (node (ref "U1") (pin "P101") (pinfunction "GND11_P101") (pintype "passive"))
      (node (ref "U1") (pin "P114") (pinfunction "GND12_P114") (pintype "passive"))
      (node (ref "U1") (pin "P117") (pinfunction "GND13_P117") (pintype "passive"))
      (node (ref "U1") (pin "P136") (pinfunction "GND14_P136") (pintype "passive"))
      (node (ref "U1") (pin "P139") (pinfunction "GND15_P139") (pintype "passive"))
      (node (ref "U1") (pin "P16") (pinfunction "GND1_P16") (pintype "passive"))
      (node (ref "U1") (pin "P22") (pinfunction "GND2_P22") (pintype "passive"))
      (node (ref "U1") (pin "P29") (pinfunction "GND3_P29") (pintype "passive"))
      (node (ref "U1") (pin "P37") (pinfunction "M1_P37") (pintype "bidirectional"))
      (node (ref "U1") (pin "P38") (pinfunction "M0_P38") (pintype "bidirectional"))
      (node (ref "U1") (pin "P39") (pinfunction "M2_P39") (pintype "bidirectional"))
      (node (ref "U1") (pin "P42") (pinfunction "GND4_P42") (pintype "passive"))
      (node (ref "U1") (pin "P45") (pinfunction "GND5_P45") (pintype "passive"))
      (node (ref "U1") (pin "P64") (pinfunction "GND6_P64") (pintype "passive"))
      (node (ref "U1") (pin "P67") (pinfunction "GND7_P67") (pintype "passive"))
      (node (ref "U1") (pin "P81") (pinfunction "GND8_P81") (pintype "passive"))
      (node (ref "U1") (pin "P88") (pinfunction "GND9_P88") (pintype "passive"))
      (node (ref "U1") (pin "P9") (pinfunction "GND0_P9") (pintype "passive"))
      (node (ref "U1") (pin "P94") (pinfunction "GND10_P94") (pintype "passive"))
      (node (ref "X1") (pin "3") (pinfunction "2_3") (pintype "passive"))
      (node (ref "X2") (pin "13") (pinfunction "13_13") (pintype "passive"))
      (node (ref "X2") (pin "14") (pinfunction "14_14") (pintype "passive"))
      (node (ref "X2") (pin "17") (pinfunction "17_17") (pintype "passive"))
      (node (ref "X2") (pin "18") (pinfunction "18_18") (pintype "passive"))
      (node (ref "X2") (pin "21") (pinfunction "21_21") (pintype "passive"))
      (node (ref "X2") (pin "4") (pinfunction "4_4") (pintype "passive"))
      (node (ref "X2") (pin "5") (pinfunction "5_5") (pintype "passive"))
      (node (ref "X2") (pin "9") (pinfunction "9_9") (pintype "passive"))
      (node (ref "X3") (pin "3") (pinfunction "3_3") (pintype "passive"))
      (node (ref "X3") (pin "SH2") (pinfunction "PE2_SH2") (pintype "power_in"))
      (node (ref "X4") (pin "8") (pinfunction "F_8") (pintype "passive"))
      (node (ref "X4") (pin "G1") (pinfunction "G1_G1") (pintype "passive"))
      (node (ref "X5") (pin "8") (pinfunction "F_8") (pintype "passive"))
      (node (ref "X5") (pin "G1") (pinfunction "G1_G1") (pintype "passive"))
    )
    (net (code "68") (name "Net-(C1-Pad2)") (class "Default")
      (node (ref "C1") (pin "2") (pinfunction "2_2") (pintype "passive"))
      (node (ref "R23") (pin "2") (pinfunction "2_2") (pintype "passive"))
      (node (ref "R48") (pin "1") (pinfunction "1_1") (pintype "passive"))
    )
    (net (code "69") (name "Net-(C2-Pad1)") (class "Default")
      (node (ref "C2") (pin "1") (pinfunction "1_1") (pintype "passive"))
      (node (ref "R17") (pin "2") (pinfunction "2_2") (pintype "passive"))
      (node (ref "X1") (pin "1") (pinfunction "1_1") (pintype "passive"))
    )
    (net (code "70") (name "Net-(C3-Pad1)") (class "Default")
      (node (ref "C3") (pin "1") (pinfunction "1_1") (pintype "passive"))
      (node (ref "R48") (pin "2") (pinfunction "2_2") (pintype "passive"))
    )
    (net (code "71") (name "Net-(C4-Pad1)") (class "Default")
      (node (ref "C4") (pin "1") (pinfunction "1_1") (pintype "passive"))
      (node (ref "R49") (pin "2") (pinfunction "2_2") (pintype "passive"))
    )
    (net (code "72") (name "Net-(C5-Pad2)") (class "Default")
      (node (ref "C5") (pin "2") (pinfunction "2_2") (pintype "passive"))
      (node (ref "R34") (pin "2") (pinfunction "2_2") (pintype "passive"))
      (node (ref "R49") (pin "1") (pinfunction "1_1") (pintype "passive"))
    )
    (net (code "73") (name "Net-(IC1-CLK)") (class "Default")
      (node (ref "IC1") (pin "3") (pinfunction "CLK_3") (pintype "bidirectional"))
      (node (ref "U1") (pin "P72") (pinfunction "CCLK_P72") (pintype "bidirectional"))
    )
    (net (code "74") (name "Net-(IC1-TDO)") (class "Default")
      (node (ref "IC1") (pin "17") (pinfunction "TDO_17") (pintype "bidirectional"))
      (node (ref "R1") (pin "2") (pinfunction "2_2") (pintype "passive"))
    )
    (net (code "75") (name "Net-(IC1-{slash}CE)") (class "Default")
      (node (ref "IC1") (pin "10") (pinfunction "/CE_10") (pintype "bidirectional"))
      (node (ref "U1") (pin "P71") (pinfunction "DONE_P71") (pintype "bidirectional"))
    )
    (net (code "76") (name "Net-(IC1-{slash}CF)") (class "Default")
      (node (ref "IC1") (pin "7") (pinfunction "/CF_7") (pintype "bidirectional"))
      (node (ref "U1") (pin "P143") (pinfunction "PROG_B_P143") (pintype "bidirectional"))
    )
    (net (code "77") (name "Net-(Q5-B)") (class "Default")
      (node (ref "Q5") (pin "1") (pinfunction "B_1") (pintype "passive"))
      (node (ref "R8") (pin "2") (pinfunction "2_2") (pintype "passive"))
    )
    (net (code "78") (name "Net-(Q5-E)") (class "Default")
      (node (ref "Q5") (pin "2") (pinfunction "E_2") (pintype "passive"))
      (node (ref "R13") (pin "2") (pinfunction "2_2") (pintype "passive"))
      (node (ref "R14") (pin "2") (pinfunction "2_2") (pintype "passive"))
    )
    (net (code "79") (name "Net-(Q6-B)") (class "Default")
      (node (ref "Q6") (pin "1") (pinfunction "B_1") (pintype "passive"))
      (node (ref "R10") (pin "2") (pinfunction "2_2") (pintype "passive"))
      (node (ref "R9") (pin "2") (pinfunction "2_2") (pintype "passive"))
    )
    (net (code "80") (name "Net-(Q6-E)") (class "Default")
      (node (ref "Q6") (pin "2") (pinfunction "E_2") (pintype "passive"))
      (node (ref "R15") (pin "2") (pinfunction "2_2") (pintype "passive"))
      (node (ref "R16") (pin "2") (pinfunction "2_2") (pintype "passive"))
      (node (ref "R20") (pin "2") (pinfunction "2_2") (pintype "passive"))
    )
    (net (code "81") (name "Net-(Q7-B)") (class "Default")
      (node (ref "Q7") (pin "1") (pinfunction "B_1") (pintype "passive"))
      (node (ref "R29") (pin "2") (pinfunction "2_2") (pintype "passive"))
      (node (ref "R30") (pin "2") (pinfunction "2_2") (pintype "passive"))
    )
    (net (code "82") (name "Net-(Q7-E)") (class "Default")
      (node (ref "Q7") (pin "2") (pinfunction "E_2") (pintype "passive"))
      (node (ref "R31") (pin "2") (pinfunction "2_2") (pintype "passive"))
      (node (ref "R32") (pin "2") (pinfunction "2_2") (pintype "passive"))
      (node (ref "R33") (pin "2") (pinfunction "2_2") (pintype "passive"))
    )
    (net (code "83") (name "Net-(Q8-B)") (class "Default")
      (node (ref "Q8") (pin "1") (pinfunction "B_1") (pintype "passive"))
      (node (ref "R24") (pin "2") (pinfunction "2_2") (pintype "passive"))
      (node (ref "R25") (pin "2") (pinfunction "2_2") (pintype "passive"))
    )
    (net (code "84") (name "Net-(Q8-E)") (class "Default")
      (node (ref "Q8") (pin "2") (pinfunction "E_2") (pintype "passive"))
      (node (ref "R26") (pin "2") (pinfunction "2_2") (pintype "passive"))
      (node (ref "R27") (pin "2") (pinfunction "2_2") (pintype "passive"))
      (node (ref "R28") (pin "2") (pinfunction "2_2") (pintype "passive"))
    )
    (net (code "85") (name "Net-(R18-Pad2)") (class "Default")
      (node (ref "R18") (pin "2") (pinfunction "2_2") (pintype "passive"))
      (node (ref "R22") (pin "2") (pinfunction "2_2") (pintype "passive"))
    )
    (net (code "86") (name "Net-(T2-B)") (class "Default")
      (node (ref "C2") (pin "2") (pinfunction "2_2") (pintype "passive"))
      (node (ref "R18") (pin "1") (pinfunction "1_1") (pintype "passive"))
      (node (ref "R19") (pin "2") (pinfunction "2_2") (pintype "passive"))
      (node (ref "T2") (pin "1") (pinfunction "B_1") (pintype "passive"))
    )
    (net (code "87") (name "Net-(U$1-A0)") (class "Default")
      (node (ref "U$1") (pin "P20") (pinfunction "A0_P20") (pintype "bidirectional"))
      (node (ref "U1") (pin "P77") (pinfunction "IO_L20P_3_P77") (pintype "bidirectional"))
    )
    (net (code "88") (name "Net-(U$1-A1)") (class "Default")
      (node (ref "U$1") (pin "P19") (pinfunction "A1_P19") (pintype "bidirectional"))
      (node (ref "U1") (pin "P76") (pinfunction "IO_P76") (pintype "bidirectional"))
    )
    (net (code "89") (name "Net-(U$1-A2)") (class "Default")
      (node (ref "U$1") (pin "P18") (pinfunction "A2_P18") (pintype "bidirectional"))
      (node (ref "U1") (pin "P74") (pinfunction "IO_L01N_3VRP_3_P74") (pintype "bidirectional"))
    )
    (net (code "90") (name "Net-(U$1-A3)") (class "Default")
      (node (ref "U$1") (pin "P17") (pinfunction "A3_P17") (pintype "bidirectional"))
      (node (ref "U1") (pin "P73") (pinfunction "IO_L01P_3VRN_3_P73") (pintype "bidirectional"))
    )
    (net (code "91") (name "Net-(U$1-A4)") (class "Default")
      (node (ref "U$1") (pin "P16") (pinfunction "A4_P16") (pintype "bidirectional"))
      (node (ref "U1") (pin "P108") (pinfunction "IO_L01N_2VRP_2_P108") (pintype "bidirectional"))
    )
    (net (code "92") (name "Net-(U$1-A5)") (class "Default")
      (node (ref "U$1") (pin "P15") (pinfunction "A5_P15") (pintype "bidirectional"))
      (node (ref "U1") (pin "P107") (pinfunction "IO_L01P_2VRN_2_P107") (pintype "bidirectional"))
    )
    (net (code "93") (name "Net-(U$1-A6)") (class "Default")
      (node (ref "U$1") (pin "P14") (pinfunction "A6_P14") (pintype "bidirectional"))
      (node (ref "U1") (pin "P105") (pinfunction "IO_L20N_2_P105") (pintype "bidirectional"))
    )
    (net (code "94") (name "Net-(U$1-A7)") (class "Default")
      (node (ref "U$1") (pin "P13") (pinfunction "A7_P13") (pintype "bidirectional"))
      (node (ref "U1") (pin "P104") (pinfunction "IO_L20P_2_P104") (pintype "bidirectional"))
    )
    (net (code "95") (name "Net-(U$1-A8)") (class "Default")
      (node (ref "U$1") (pin "P3") (pinfunction "A8_P3") (pintype "bidirectional"))
      (node (ref "U1") (pin "P93") (pinfunction "IO_L40N_2_P93") (pintype "bidirectional"))
    )
    (net (code "96") (name "Net-(U$1-A9)") (class "Default")
      (node (ref "U$1") (pin "P2") (pinfunction "A9_P2") (pintype "bidirectional"))
      (node (ref "U1") (pin "P92") (pinfunction "IO_L40P_2VREF_2_P92") (pintype "bidirectional"))
    )
    (net (code "97") (name "Net-(U$1-A10)") (class "Default")
      (node (ref "U$1") (pin "P31") (pinfunction "A10_P31") (pintype "bidirectional"))
      (node (ref "U1") (pin "P87") (pinfunction "IO_L24N_3_P87") (pintype "bidirectional"))
    )
    (net (code "98") (name "Net-(U$1-A11)") (class "Default")
      (node (ref "U$1") (pin "P1") (pinfunction "A11_P1") (pintype "bidirectional"))
      (node (ref "U1") (pin "P90") (pinfunction "IO_L40N_3VREF_3_P90") (pintype "bidirectional"))
    )
    (net (code "99") (name "Net-(U$1-A12)") (class "Default")
      (node (ref "U$1") (pin "P12") (pinfunction "A12_P12") (pintype "bidirectional"))
      (node (ref "U1") (pin "P103") (pinfunction "IO_L21N_2_P103") (pintype "bidirectional"))
    )
    (net (code "100") (name "Net-(U$1-A13)") (class "Default")
      (node (ref "U$1") (pin "P4") (pinfunction "A13_P4") (pintype "bidirectional"))
      (node (ref "U1") (pin "P95") (pinfunction "IO_L24P_2_P95") (pintype "bidirectional"))
    )
    (net (code "101") (name "Net-(U$1-A14)") (class "Default")
      (node (ref "U$1") (pin "P11") (pinfunction "A14_P11") (pintype "bidirectional"))
      (node (ref "U1") (pin "P102") (pinfunction "IO_L21P_2_P102") (pintype "bidirectional"))
    )
    (net (code "102") (name "Net-(U$1-A15)") (class "Default")
      (node (ref "U$1") (pin "P7") (pinfunction "A15_P7") (pintype "bidirectional"))
      (node (ref "U1") (pin "P98") (pinfunction "IO_L23N_2VREF_2_P98") (pintype "bidirectional"))
    )
    (net (code "103") (name "Net-(U$1-A16)") (class "Default")
      (node (ref "U$1") (pin "P10") (pinfunction "A16_P10") (pintype "bidirectional"))
      (node (ref "U1") (pin "P100") (pinfunction "IO_L22N_2_P100") (pintype "bidirectional"))
    )
    (net (code "104") (name "Net-(U$1-A17)") (class "Default")
      (node (ref "U$1") (pin "P6") (pinfunction "A17_P6") (pintype "bidirectional"))
      (node (ref "U1") (pin "P97") (pinfunction "IO_L23P_2_P97") (pintype "bidirectional"))
    )
    (net (code "105") (name "Net-(U$1-A18)") (class "Default")
      (node (ref "U$1") (pin "P9") (pinfunction "A18_P9") (pintype "bidirectional"))
      (node (ref "U1") (pin "P99") (pinfunction "IO_L22P_2_P99") (pintype "bidirectional"))
    )
    (net (code "106") (name "Net-(U$1-DQ0)") (class "Default")
      (node (ref "U$1") (pin "P21") (pinfunction "DQ0_P21") (pintype "bidirectional"))
      (node (ref "U1") (pin "P78") (pinfunction "IO_L20N_3_P78") (pintype "bidirectional"))
    )
    (net (code "107") (name "Net-(U$1-DQ1)") (class "Default")
      (node (ref "U$1") (pin "P22") (pinfunction "DQ1_P22") (pintype "bidirectional"))
      (node (ref "U1") (pin "P79") (pinfunction "IO_L21P_3_P79") (pintype "bidirectional"))
    )
    (net (code "108") (name "Net-(U$1-DQ2)") (class "Default")
      (node (ref "U$1") (pin "P23") (pinfunction "DQ2_P23") (pintype "bidirectional"))
      (node (ref "U1") (pin "P80") (pinfunction "IO_L21N_3_P80") (pintype "bidirectional"))
    )
    (net (code "109") (name "Net-(U$1-DQ3)") (class "Default")
      (node (ref "U$1") (pin "P25") (pinfunction "DQ3_P25") (pintype "bidirectional"))
      (node (ref "U1") (pin "P82") (pinfunction "IO_L22P_3_P82") (pintype "bidirectional"))
    )
    (net (code "110") (name "Net-(U$1-DQ4)") (class "Default")
      (node (ref "U$1") (pin "P26") (pinfunction "DQ4_P26") (pintype "bidirectional"))
      (node (ref "U1") (pin "P83") (pinfunction "IO_L22N_3_P83") (pintype "bidirectional"))
    )
    (net (code "111") (name "Net-(U$1-DQ5)") (class "Default")
      (node (ref "U$1") (pin "P27") (pinfunction "DQ5_P27") (pintype "bidirectional"))
      (node (ref "U1") (pin "P84") (pinfunction "IO_L23P_3VREF_3_P84") (pintype "bidirectional"))
    )
    (net (code "112") (name "Net-(U$1-DQ6)") (class "Default")
      (node (ref "U$1") (pin "P28") (pinfunction "DQ6_P28") (pintype "bidirectional"))
      (node (ref "U1") (pin "P85") (pinfunction "IO_L23N_3_P85") (pintype "bidirectional"))
    )
    (net (code "113") (name "Net-(U$1-DQ7)") (class "Default")
      (node (ref "U$1") (pin "P29") (pinfunction "DQ7_P29") (pintype "bidirectional"))
      (node (ref "U1") (pin "P86") (pinfunction "IO_L24P_3_P86") (pintype "bidirectional"))
    )
    (net (code "114") (name "Net-(U$1-OE)") (class "Default")
      (node (ref "U$1") (pin "P32") (pinfunction "OE_P32") (pintype "bidirectional"))
      (node (ref "U1") (pin "P89") (pinfunction "IO_L40P_3_P89") (pintype "bidirectional"))
    )
    (net (code "115") (name "Net-(U$1-WE)") (class "Default")
      (node (ref "U$1") (pin "P5") (pinfunction "WE_P5") (pintype "bidirectional"))
      (node (ref "U1") (pin "P96") (pinfunction "IO_L24N_2_P96") (pintype "bidirectional"))
    )
    (net (code "116") (name "Net-(U1N-TCK)") (class "Default")
      (node (ref "R2") (pin "1") (pinfunction "1_1") (pintype "passive"))
      (node (ref "U1") (pin "P110") (pinfunction "TCK_P110") (pintype "bidirectional"))
    )
    (net (code "117") (name "Net-(U1N-TDI)") (class "Default")
      (node (ref "R1") (pin "1") (pinfunction "1_1") (pintype "passive"))
      (node (ref "U1") (pin "P144") (pinfunction "TDI_P144") (pintype "bidirectional"))
    )
    (net (code "118") (name "Net-(U1N-TMS)") (class "Default")
      (node (ref "R3") (pin "1") (pinfunction "1_1") (pintype "passive"))
      (node (ref "U1") (pin "P111") (pinfunction "TMS_P111") (pintype "bidirectional"))
    )
    (net (code "119") (name "Net-(X4A-F)") (class "Default")
      (node (ref "R40") (pin "2") (pinfunction "2_2") (pintype "passive"))
      (node (ref "X4") (pin "1") (pinfunction "F_1") (pintype "passive"))
    )
    (net (code "120") (name "Net-(X4B-F)") (class "Default")
      (node (ref "R41") (pin "2") (pinfunction "2_2") (pintype "passive"))
      (node (ref "X4") (pin "2") (pinfunction "F_2") (pintype "passive"))
    )
    (net (code "121") (name "Net-(X4C-F)") (class "Default")
      (node (ref "R42") (pin "2") (pinfunction "2_2") (pintype "passive"))
      (node (ref "X4") (pin "3") (pinfunction "F_3") (pintype "passive"))
    )
    (net (code "122") (name "Net-(X4D-F)") (class "Default")
      (node (ref "R43") (pin "2") (pinfunction "2_2") (pintype "passive"))
      (node (ref "X4") (pin "4") (pinfunction "F_4") (pintype "passive"))
    )
    (net (code "123") (name "Net-(X4F-F)") (class "Default")
      (node (ref "R44") (pin "2") (pinfunction "2_2") (pintype "passive"))
      (node (ref "X4") (pin "6") (pinfunction "F_6") (pintype "passive"))
    )
    (net (code "124") (name "Net-(X4G-F)") (class "Default")
      (node (ref "R45") (pin "2") (pinfunction "2_2") (pintype "passive"))
      (node (ref "X4") (pin "7") (pinfunction "F_7") (pintype "passive"))
    )
    (net (code "125") (name "Net-(X5A-F)") (class "Default")
      (node (ref "R46") (pin "1") (pinfunction "1_1") (pintype "passive"))
      (node (ref "X5") (pin "1") (pinfunction "F_1") (pintype "passive"))
    )
    (net (code "126") (name "Net-(X5B-F)") (class "Default")
      (node (ref "R39") (pin "1") (pinfunction "1_1") (pintype "passive"))
      (node (ref "X5") (pin "2") (pinfunction "F_2") (pintype "passive"))
    )
    (net (code "127") (name "Net-(X5C-F)") (class "Default")
      (node (ref "R38") (pin "1") (pinfunction "1_1") (pintype "passive"))
      (node (ref "X5") (pin "3") (pinfunction "F_3") (pintype "passive"))
    )
    (net (code "128") (name "Net-(X5D-F)") (class "Default")
      (node (ref "R37") (pin "1") (pinfunction "1_1") (pintype "passive"))
      (node (ref "X5") (pin "4") (pinfunction "F_4") (pintype "passive"))
    )
    (net (code "129") (name "Net-(X5F-F)") (class "Default")
      (node (ref "R36") (pin "1") (pinfunction "1_1") (pintype "passive"))
      (node (ref "X5") (pin "6") (pinfunction "F_6") (pintype "passive"))
    )
    (net (code "130") (name "Net-(X5G-F)") (class "Default")
      (node (ref "R35") (pin "1") (pinfunction "1_1") (pintype "passive"))
      (node (ref "X5") (pin "7") (pinfunction "F_7") (pintype "passive"))
    )
    (net (code "131") (name "unconnected-(IC1-NC.1-Pad2)") (class "Default")
      (node (ref "IC1") (pin "2") (pinfunction "NC.1_2") (pintype "bidirectional"))
    )
    (net (code "132") (name "unconnected-(IC1-NC.2-Pad9)") (class "Default")
      (node (ref "IC1") (pin "9") (pinfunction "NC.2_9") (pintype "bidirectional"))
    )
    (net (code "133") (name "unconnected-(IC1-NC.3-Pad12)") (class "Default")
      (node (ref "IC1") (pin "12") (pinfunction "NC.3_12") (pintype "bidirectional"))
    )
    (net (code "134") (name "unconnected-(IC1-NC.4-Pad14)") (class "Default")
      (node (ref "IC1") (pin "14") (pinfunction "NC.4_14") (pintype "bidirectional"))
    )
    (net (code "135") (name "unconnected-(IC1-NC.5-Pad15)") (class "Default")
      (node (ref "IC1") (pin "15") (pinfunction "NC.5_15") (pintype "bidirectional"))
    )
    (net (code "136") (name "unconnected-(IC1-NC.6-Pad16)") (class "Default")
      (node (ref "IC1") (pin "16") (pinfunction "NC.6_16") (pintype "bidirectional"))
    )
    (net (code "137") (name "unconnected-(IC1-{slash}CEO-Pad13)") (class "Default")
      (node (ref "IC1") (pin "13") (pinfunction "/CEO_13") (pintype "bidirectional"))
    )
    (net (code "138") (name "unconnected-(IC3-AVCC-Pad32)") (class "Default")
      (node (ref "IC3") (pin "32") (pinfunction "AVCC_32") (pintype "bidirectional"))
    )
    (net (code "139") (name "unconnected-(IC3-D+-Pad29)") (class "Default")
      (node (ref "IC3") (pin "29") (pinfunction "D+_29") (pintype "bidirectional"))
    )
    (net (code "140") (name "unconnected-(IC3-D--Pad30)") (class "Default")
      (node (ref "IC3") (pin "30") (pinfunction "D-_30") (pintype "bidirectional"))
    )
    (net (code "141") (name "unconnected-(IC3-GND-Pad3)") (class "Default")
      (node (ref "IC3") (pin "3") (pinfunction "GND_3") (pintype "bidirectional"))
    )
    (net (code "142") (name "unconnected-(IC3-PB4(T1{slash}PCINT4)-Pad18)") (class "Default")
      (node (ref "IC3") (pin "18") (pinfunction "PB4(T1/PCINT4)_18") (pintype "bidirectional"))
    )
    (net (code "143") (name "unconnected-(IC3-PB5(PCINT5)-Pad19)") (class "Default")
      (node (ref "IC3") (pin "19") (pinfunction "PB5(PCINT5)_19") (pintype "bidirectional"))
    )
    (net (code "144") (name "unconnected-(IC3-PB6(PCINT6)-Pad20)") (class "Default")
      (node (ref "IC3") (pin "20") (pinfunction "PB6(PCINT6)_20") (pintype "bidirectional"))
    )
    (net (code "145") (name "unconnected-(IC3-PB7(OC0A{slash}OC1C{slash}PCINT7)-Pad21)") (class "Default")
      (node (ref "IC3") (pin "21") (pinfunction "PB7(OC0A/OC1C/PCINT7)_21") (pintype "bidirectional"))
    )
    (net (code "146") (name "unconnected-(IC3-PC2(AIN2{slash}PCIN11)-Pad5)") (class "Default")
      (node (ref "IC3") (pin "5") (pinfunction "PC2(AIN2/PCIN11)_5") (pintype "bidirectional"))
    )
    (net (code "147") (name "unconnected-(IC3-PC4(PCINT10)-Pad26)") (class "Default")
      (node (ref "IC3") (pin "26") (pinfunction "PC4(PCINT10)_26") (pintype "bidirectional"))
    )
    (net (code "148") (name "unconnected-(IC3-PC5(OC1B{slash}PCINT9)-Pad25)") (class "Default")
      (node (ref "IC3") (pin "25") (pinfunction "PC5(OC1B/PCINT9)_25") (pintype "bidirectional"))
    )
    (net (code "149") (name "unconnected-(IC3-PC6(OC1A{slash}PCINT8)-Pad23)") (class "Default")
      (node (ref "IC3") (pin "23") (pinfunction "PC6(OC1A/PCINT8)_23") (pintype "bidirectional"))
    )
    (net (code "150") (name "unconnected-(IC3-PC7(ICP1{slash}INT4{slash}CLKO)-Pad22)") (class "Default")
      (node (ref "IC3") (pin "22") (pinfunction "PC7(ICP1/INT4/CLKO)_22") (pintype "bidirectional"))
    )
    (net (code "151") (name "unconnected-(IC3-PD0(INT0{slash}OC0B)-Pad6)") (class "Default")
      (node (ref "IC3") (pin "6") (pinfunction "PD0(INT0/OC0B)_6") (pintype "bidirectional"))
    )
    (net (code "152") (name "unconnected-(IC3-PD1(INT1{slash}AIN0)-Pad7)") (class "Default")
      (node (ref "IC3") (pin "7") (pinfunction "PD1(INT1/AIN0)_7") (pintype "bidirectional"))
    )
    (net (code "153") (name "unconnected-(IC3-PD4(INT5{slash}AIN3)-Pad10)") (class "Default")
      (node (ref "IC3") (pin "10") (pinfunction "PD4(INT5/AIN3)_10") (pintype "bidirectional"))
    )
    (net (code "154") (name "unconnected-(IC3-PD5(XCK{slash}AIN4{slash}PCINT12)-Pad11)") (class "Default")
      (node (ref "IC3") (pin "11") (pinfunction "PD5(XCK/AIN4/PCINT12)_11") (pintype "bidirectional"))
    )
    (net (code "155") (name "unconnected-(IC3-PD6(INT6{slash}AIN5{slash}RTS)-Pad12)") (class "Default")
      (node (ref "IC3") (pin "12") (pinfunction "PD6(INT6/AIN5/RTS)_12") (pintype "bidirectional"))
    )
    (net (code "156") (name "unconnected-(IC3-UCAP-Pad27)") (class "Default")
      (node (ref "IC3") (pin "27") (pinfunction "UCAP_27") (pintype "bidirectional"))
    )
    (net (code "157") (name "unconnected-(IC3-UGND-Pad28)") (class "Default")
      (node (ref "IC3") (pin "28") (pinfunction "UGND_28") (pintype "bidirectional"))
    )
    (net (code "158") (name "unconnected-(IC3-UVCC-Pad31)") (class "Default")
      (node (ref "IC3") (pin "31") (pinfunction "UVCC_31") (pintype "bidirectional"))
    )
    (net (code "159") (name "unconnected-(IC3-VCC-Pad4)") (class "Default")
      (node (ref "IC3") (pin "4") (pinfunction "VCC_4") (pintype "bidirectional"))
    )
    (net (code "160") (name "unconnected-(IC3-XTAL1-Pad1)") (class "Default")
      (node (ref "IC3") (pin "1") (pinfunction "XTAL1_1") (pintype "bidirectional"))
    )
    (net (code "161") (name "unconnected-(IC3-XTAL2{slash}PC0-Pad2)") (class "Default")
      (node (ref "IC3") (pin "2") (pinfunction "XTAL2/PC0_2") (pintype "bidirectional"))
    )
    (net (code "162") (name "unconnected-(IC3-{slash}RESET(PC1)-Pad24)") (class "Default")
      (node (ref "IC3") (pin "24") (pinfunction "/RESET(PC1)_24") (pintype "bidirectional"))
    )
    (net (code "163") (name "unconnected-(REG1.2-VOUT2-Pad2)") (class "Default")
      (node (ref "REG1.2") (pin "2") (pinfunction "VOUT2_2") (pintype "bidirectional"))
    )
    (net (code "164") (name "unconnected-(U$2-TRI-PadENA)") (class "Default")
      (node (ref "U$2") (pin "ENA") (pinfunction "TRI_ENA") (pintype "input"))
    )
    (net (code "165") (name "unconnected-(U1A-IO_L27P_0-PadP135)") (class "Default")
      (node (ref "U1") (pin "P135") (pinfunction "IO_L27P_0_P135") (pintype "bidirectional"))
    )
    (net (code "166") (name "unconnected-(U1A-IO_L30N_0-PadP132)") (class "Default")
      (node (ref "U1") (pin "P132") (pinfunction "IO_L30N_0_P132") (pintype "bidirectional"))
    )
    (net (code "167") (name "unconnected-(U1A-IO_L30P_0-PadP131)") (class "Default")
      (node (ref "U1") (pin "P131") (pinfunction "IO_L30P_0_P131") (pintype "bidirectional"))
    )
    (net (code "168") (name "unconnected-(U1A-IO_L31N_0-PadP130)") (class "Default")
      (node (ref "U1") (pin "P130") (pinfunction "IO_L31N_0_P130") (pintype "bidirectional"))
    )
    (net (code "169") (name "unconnected-(U1A-IO_L31P_0VREF_0-PadP129)") (class "Default")
      (node (ref "U1") (pin "P129") (pinfunction "IO_L31P_0VREF_0_P129") (pintype "bidirectional"))
    )
    (net (code "170") (name "unconnected-(U1A-IO_L32N_0GCLK7-PadP128)") (class "Default")
      (node (ref "U1") (pin "P128") (pinfunction "IO_L32N_0GCLK7_P128") (pintype "bidirectional"))
    )
    (net (code "171") (name "unconnected-(U1A-IO_L32P_0GCLK6-PadP127)") (class "Default")
      (node (ref "U1") (pin "P127") (pinfunction "IO_L32P_0GCLK6_P127") (pintype "bidirectional"))
    )
    (net (code "172") (name "unconnected-(U1C-IO-PadP116)") (class "Default")
      (node (ref "U1") (pin "P116") (pinfunction "IO_P116") (pintype "bidirectional"))
    )
    (net (code "173") (name "unconnected-(U1C-IO_L01N_1VRP_1-PadP113)") (class "Default")
      (node (ref "U1") (pin "P113") (pinfunction "IO_L01N_1VRP_1_P113") (pintype "bidirectional"))
    )
    (net (code "174") (name "unconnected-(U1C-IO_L01P_1VRN_1-PadP112)") (class "Default")
      (node (ref "U1") (pin "P112") (pinfunction "IO_L01P_1VRN_1_P112") (pintype "bidirectional"))
    )
    (net (code "175") (name "unconnected-(U1C-IO_L28N_1-PadP119)") (class "Default")
      (node (ref "U1") (pin "P119") (pinfunction "IO_L28N_1_P119") (pintype "bidirectional"))
    )
    (net (code "176") (name "unconnected-(U1C-IO_L28P_1-PadP118)") (class "Default")
      (node (ref "U1") (pin "P118") (pinfunction "IO_L28P_1_P118") (pintype "bidirectional"))
    )
    (net (code "177") (name "unconnected-(U1C-IO_L31N_1VREF_1-PadP123)") (class "Default")
      (node (ref "U1") (pin "P123") (pinfunction "IO_L31N_1VREF_1_P123") (pintype "bidirectional"))
    )
    (net (code "178") (name "unconnected-(U1C-IO_L31P_1-PadP122)") (class "Default")
      (node (ref "U1") (pin "P122") (pinfunction "IO_L31P_1_P122") (pintype "bidirectional"))
    )
    (net (code "179") (name "unconnected-(U1C-IO_L32N_1GCLK5-PadP125)") (class "Default")
      (node (ref "U1") (pin "P125") (pinfunction "IO_L32N_1GCLK5_P125") (pintype "bidirectional"))
    )
    (net (code "180") (name "unconnected-(U1C-IO_L32P_1GCLK4-PadP124)") (class "Default")
      (node (ref "U1") (pin "P124") (pinfunction "IO_L32P_1GCLK4_P124") (pintype "bidirectional"))
    )
    (net (code "181") (name "unconnected-(U1J-IO_L01N_6VRP_6-PadP36)") (class "Default")
      (node (ref "U1") (pin "P36") (pinfunction "IO_L01N_6VRP_6_P36") (pintype "bidirectional"))
    )
    (net (code "182") (name "unconnected-(U1J-IO_L01P_6VRN_6-PadP35)") (class "Default")
      (node (ref "U1") (pin "P35") (pinfunction "IO_L01P_6VRN_6_P35") (pintype "bidirectional"))
    )
    (net (code "183") (name "unconnected-(U1J-IO_L20N_6-PadP33)") (class "Default")
      (node (ref "U1") (pin "P33") (pinfunction "IO_L20N_6_P33") (pintype "bidirectional"))
    )
    (net (code "184") (name "unconnected-(U1J-IO_L20P_6-PadP32)") (class "Default")
      (node (ref "U1") (pin "P32") (pinfunction "IO_L20P_6_P32") (pintype "bidirectional"))
    )
    (net (code "185") (name "unconnected-(U1J-IO_L21N_6-PadP31)") (class "Default")
      (node (ref "U1") (pin "P31") (pinfunction "IO_L21N_6_P31") (pintype "bidirectional"))
    )
    (net (code "186") (name "unconnected-(U1J-IO_L21P_6-PadP30)") (class "Default")
      (node (ref "U1") (pin "P30") (pinfunction "IO_L21P_6_P30") (pintype "bidirectional"))
    )
    (net (code "187") (name "unconnected-(U1J-IO_L22N_6-PadP28)") (class "Default")
      (node (ref "U1") (pin "P28") (pinfunction "IO_L22N_6_P28") (pintype "bidirectional"))
    )
    (net (code "188") (name "unconnected-(U1J-IO_L22P_6-PadP27)") (class "Default")
      (node (ref "U1") (pin "P27") (pinfunction "IO_L22P_6_P27") (pintype "bidirectional"))
    )
    (net (code "189") (name "unconnected-(U1J-IO_L23N_6-PadP26)") (class "Default")
      (node (ref "U1") (pin "P26") (pinfunction "IO_L23N_6_P26") (pintype "bidirectional"))
    )
    (net (code "190") (name "unconnected-(U1J-IO_L23P_6-PadP25)") (class "Default")
      (node (ref "U1") (pin "P25") (pinfunction "IO_L23P_6_P25") (pintype "bidirectional"))
    )
    (net (code "191") (name "unconnected-(U1J-IO_L24N_6VREF_6-PadP24)") (class "Default")
      (node (ref "U1") (pin "P24") (pinfunction "IO_L24N_6VREF_6_P24") (pintype "bidirectional"))
    )
    (net (code "192") (name "unconnected-(U1J-IO_L24P_6-PadP23)") (class "Default")
      (node (ref "U1") (pin "P23") (pinfunction "IO_L24P_6_P23") (pintype "bidirectional"))
    )
    (net (code "193") (name "unconnected-(U1J-IO_L40N_6-PadP21)") (class "Default")
      (node (ref "U1") (pin "P21") (pinfunction "IO_L40N_6_P21") (pintype "bidirectional"))
    )
    (net (code "194") (name "unconnected-(U1J-IO_L40P_6VREF_6-PadP20)") (class "Default")
      (node (ref "U1") (pin "P20") (pinfunction "IO_L40P_6VREF_6_P20") (pintype "bidirectional"))
    )
    (net (code "195") (name "unconnected-(U1L-IOVREF_7-PadP4)") (class "Default")
      (node (ref "U1") (pin "P4") (pinfunction "IOVREF_7_P4") (pintype "bidirectional"))
    )
    (net (code "196") (name "unconnected-(U1L-IO_L01N_7VRP_7-PadP2)") (class "Default")
      (node (ref "U1") (pin "P2") (pinfunction "IO_L01N_7VRP_7_P2") (pintype "bidirectional"))
    )
    (net (code "197") (name "unconnected-(U1L-IO_L01P_7VRN_7-PadP1)") (class "Default")
      (node (ref "U1") (pin "P1") (pinfunction "IO_L01P_7VRN_7_P1") (pintype "bidirectional"))
    )
    (net (code "198") (name "unconnected-(U1L-IO_L20N_7-PadP6)") (class "Default")
      (node (ref "U1") (pin "P6") (pinfunction "IO_L20N_7_P6") (pintype "bidirectional"))
    )
    (net (code "199") (name "unconnected-(U1L-IO_L20P_7-PadP5)") (class "Default")
      (node (ref "U1") (pin "P5") (pinfunction "IO_L20P_7_P5") (pintype "bidirectional"))
    )
    (net (code "200") (name "unconnected-(U1L-IO_L21N_7-PadP8)") (class "Default")
      (node (ref "U1") (pin "P8") (pinfunction "IO_L21N_7_P8") (pintype "bidirectional"))
    )
    (net (code "201") (name "unconnected-(U1L-IO_L21P_7-PadP7)") (class "Default")
      (node (ref "U1") (pin "P7") (pinfunction "IO_L21P_7_P7") (pintype "bidirectional"))
    )
    (net (code "202") (name "unconnected-(U1L-IO_L22N_7-PadP11)") (class "Default")
      (node (ref "U1") (pin "P11") (pinfunction "IO_L22N_7_P11") (pintype "bidirectional"))
    )
    (net (code "203") (name "unconnected-(U1L-IO_L22P_7-PadP10)") (class "Default")
      (node (ref "U1") (pin "P10") (pinfunction "IO_L22P_7_P10") (pintype "bidirectional"))
    )
    (net (code "204") (name "unconnected-(U1L-IO_L23N_7-PadP13)") (class "Default")
      (node (ref "U1") (pin "P13") (pinfunction "IO_L23N_7_P13") (pintype "bidirectional"))
    )
    (net (code "205") (name "unconnected-(U1L-IO_L23P_7-PadP12)") (class "Default")
      (node (ref "U1") (pin "P12") (pinfunction "IO_L23P_7_P12") (pintype "bidirectional"))
    )
    (net (code "206") (name "unconnected-(U1L-IO_L24N_7-PadP15)") (class "Default")
      (node (ref "U1") (pin "P15") (pinfunction "IO_L24N_7_P15") (pintype "bidirectional"))
    )
    (net (code "207") (name "unconnected-(U1L-IO_L24P_7-PadP14)") (class "Default")
      (node (ref "U1") (pin "P14") (pinfunction "IO_L24P_7_P14") (pintype "bidirectional"))
    )
    (net (code "208") (name "unconnected-(U1L-IO_L40N_7VREF_7-PadP18)") (class "Default")
      (node (ref "U1") (pin "P18") (pinfunction "IO_L40N_7VREF_7_P18") (pintype "bidirectional"))
    )
    (net (code "209") (name "unconnected-(U1L-IO_L40P_7-PadP17)") (class "Default")
      (node (ref "U1") (pin "P17") (pinfunction "IO_L40P_7_P17") (pintype "bidirectional"))
    )
    (net (code "210") (name "unconnected-(U1N-HSWAP_EN-PadP142)") (class "Default")
      (node (ref "U1") (pin "P142") (pinfunction "HSWAP_EN_P142") (pintype "bidirectional"))
    )
    (net (code "211") (name "unconnected-(X1-3-Pad2)") (class "Default")
      (node (ref "X1") (pin "2") (pinfunction "3_2") (pintype "passive"))
    )
    (net (code "212") (name "unconnected-(X2-Pad10)") (class "Default")
      (node (ref "X2") (pin "10") (pinfunction "10_10") (pintype "passive"))
    )
    (net (code "213") (name "unconnected-(X2-Pad12)") (class "Default")
      (node (ref "X2") (pin "12") (pinfunction "12_12") (pintype "passive"))
    )
    (net (code "214") (name "unconnected-(X3-Pad2)") (class "Default")
      (node (ref "X3") (pin "2") (pinfunction "2_2") (pintype "passive"))
    )
    (net (code "215") (name "unconnected-(X3-Pad8)") (class "Default")
      (node (ref "X3") (pin "8") (pinfunction "8_8") (pintype "passive"))
    )
    (net (code "216") (name "unconnected-(X4-PadG2)") (class "Default")
      (node (ref "X4") (pin "G2") (pinfunction "G2_G2") (pintype "passive"))
    )
    (net (code "217") (name "unconnected-(X5-PadG2)") (class "Default")
      (node (ref "X5") (pin "G2") (pinfunction "G2_G2") (pintype "passive"))
    )
  )
)
